# board.net
KiCad netlist of a schematic drawn in EAGLE
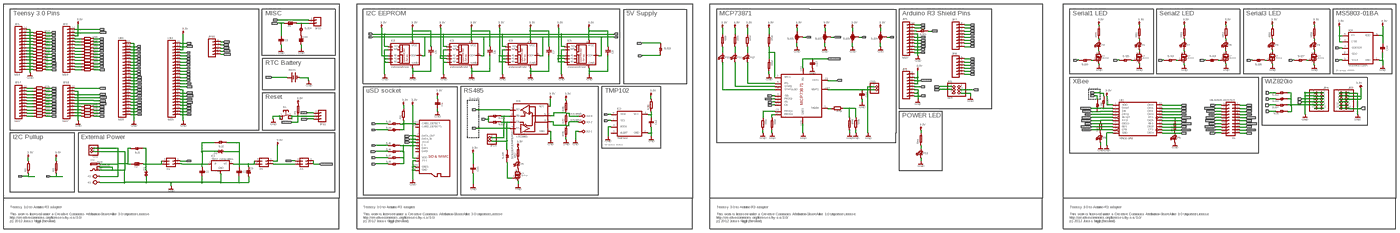
[diagram p0: schematic, sheet 1, overview]
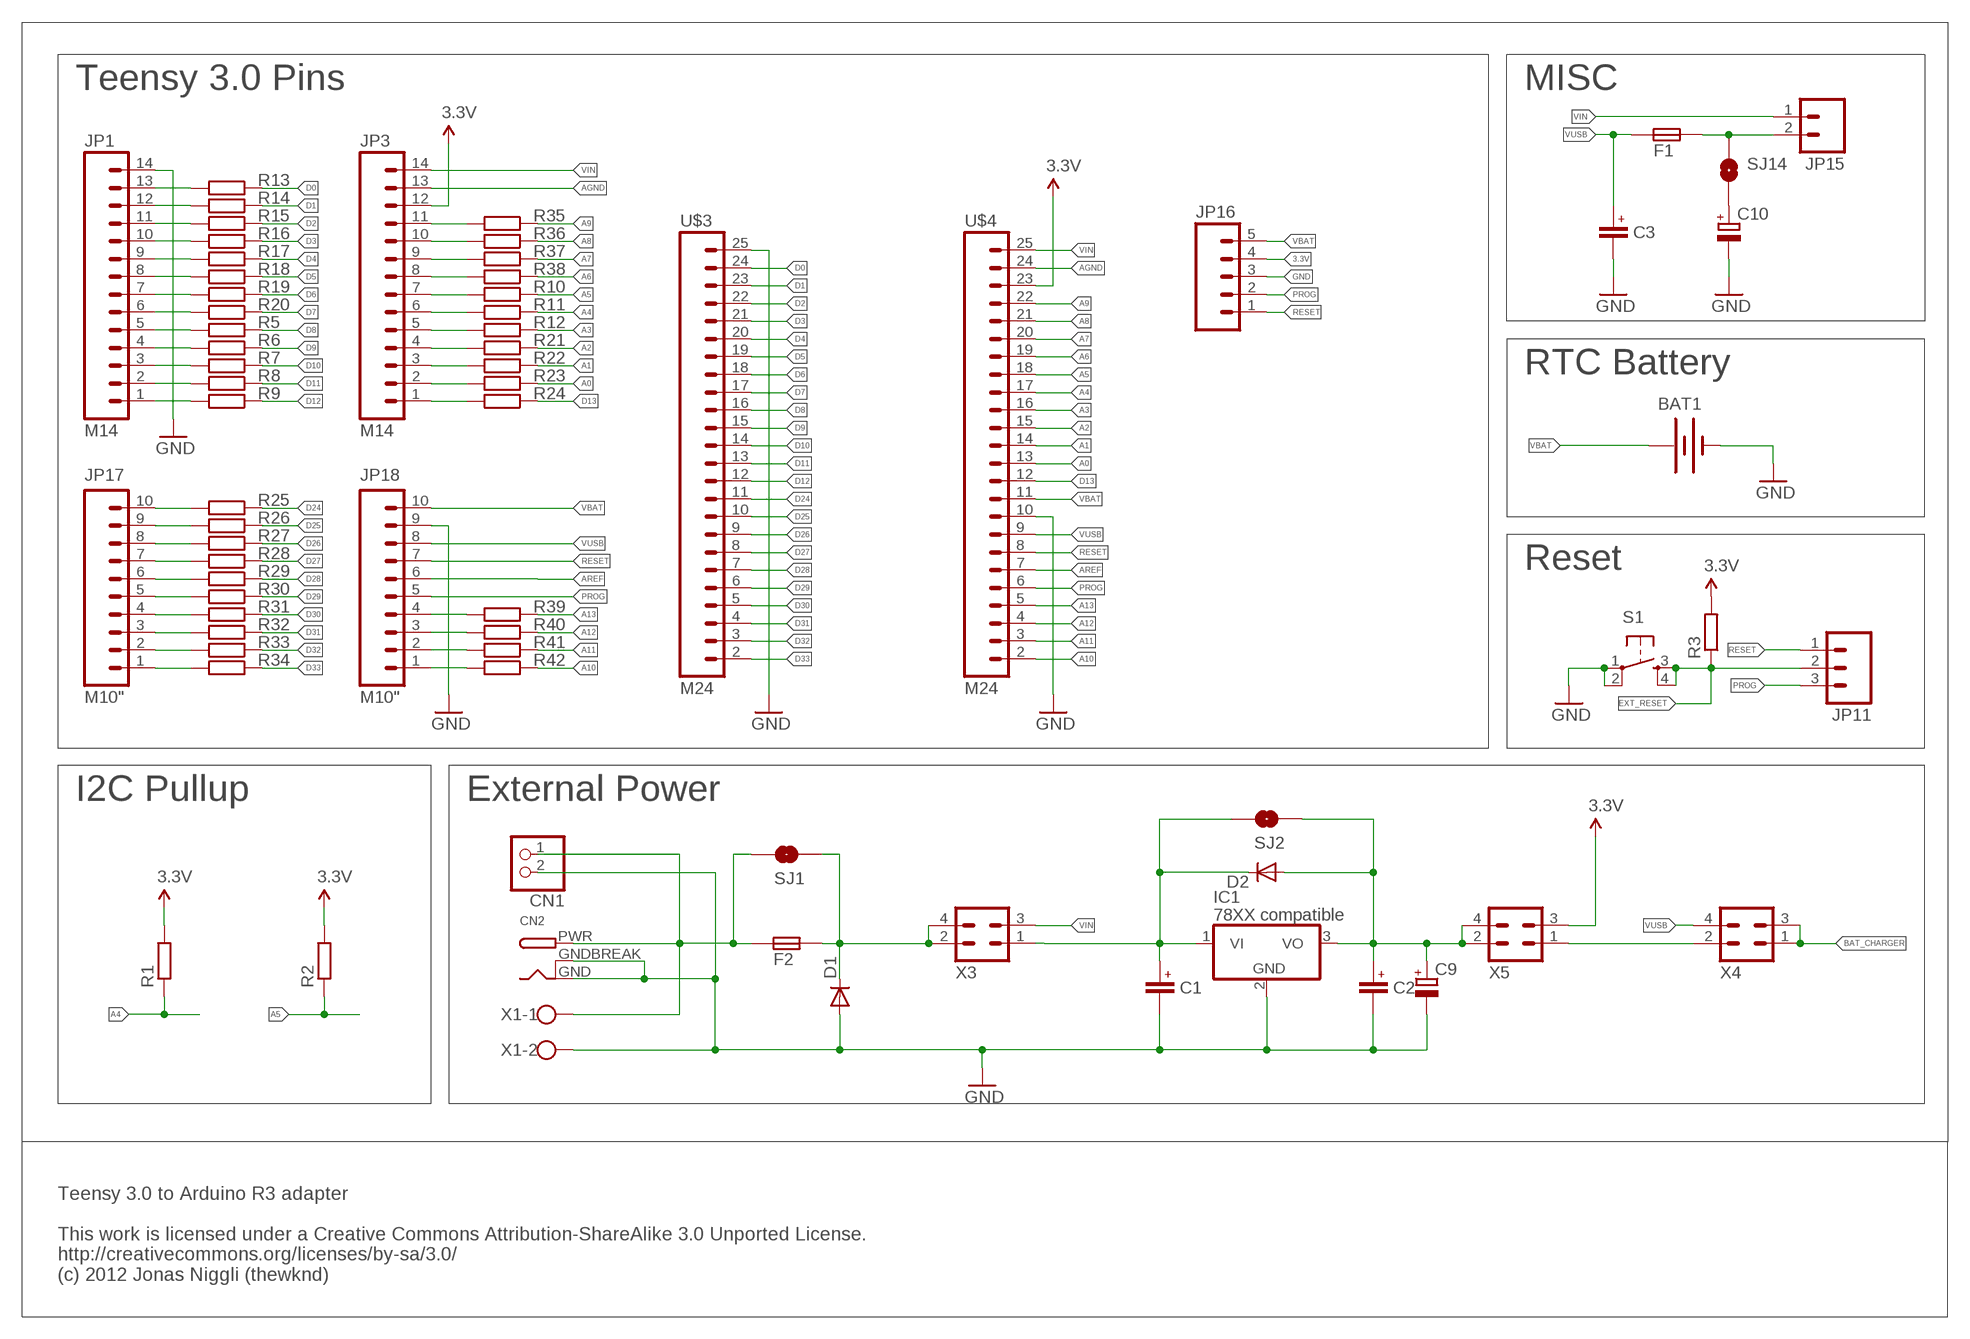
[diagram p1: schematic, sheet 1, part 1 of 4]
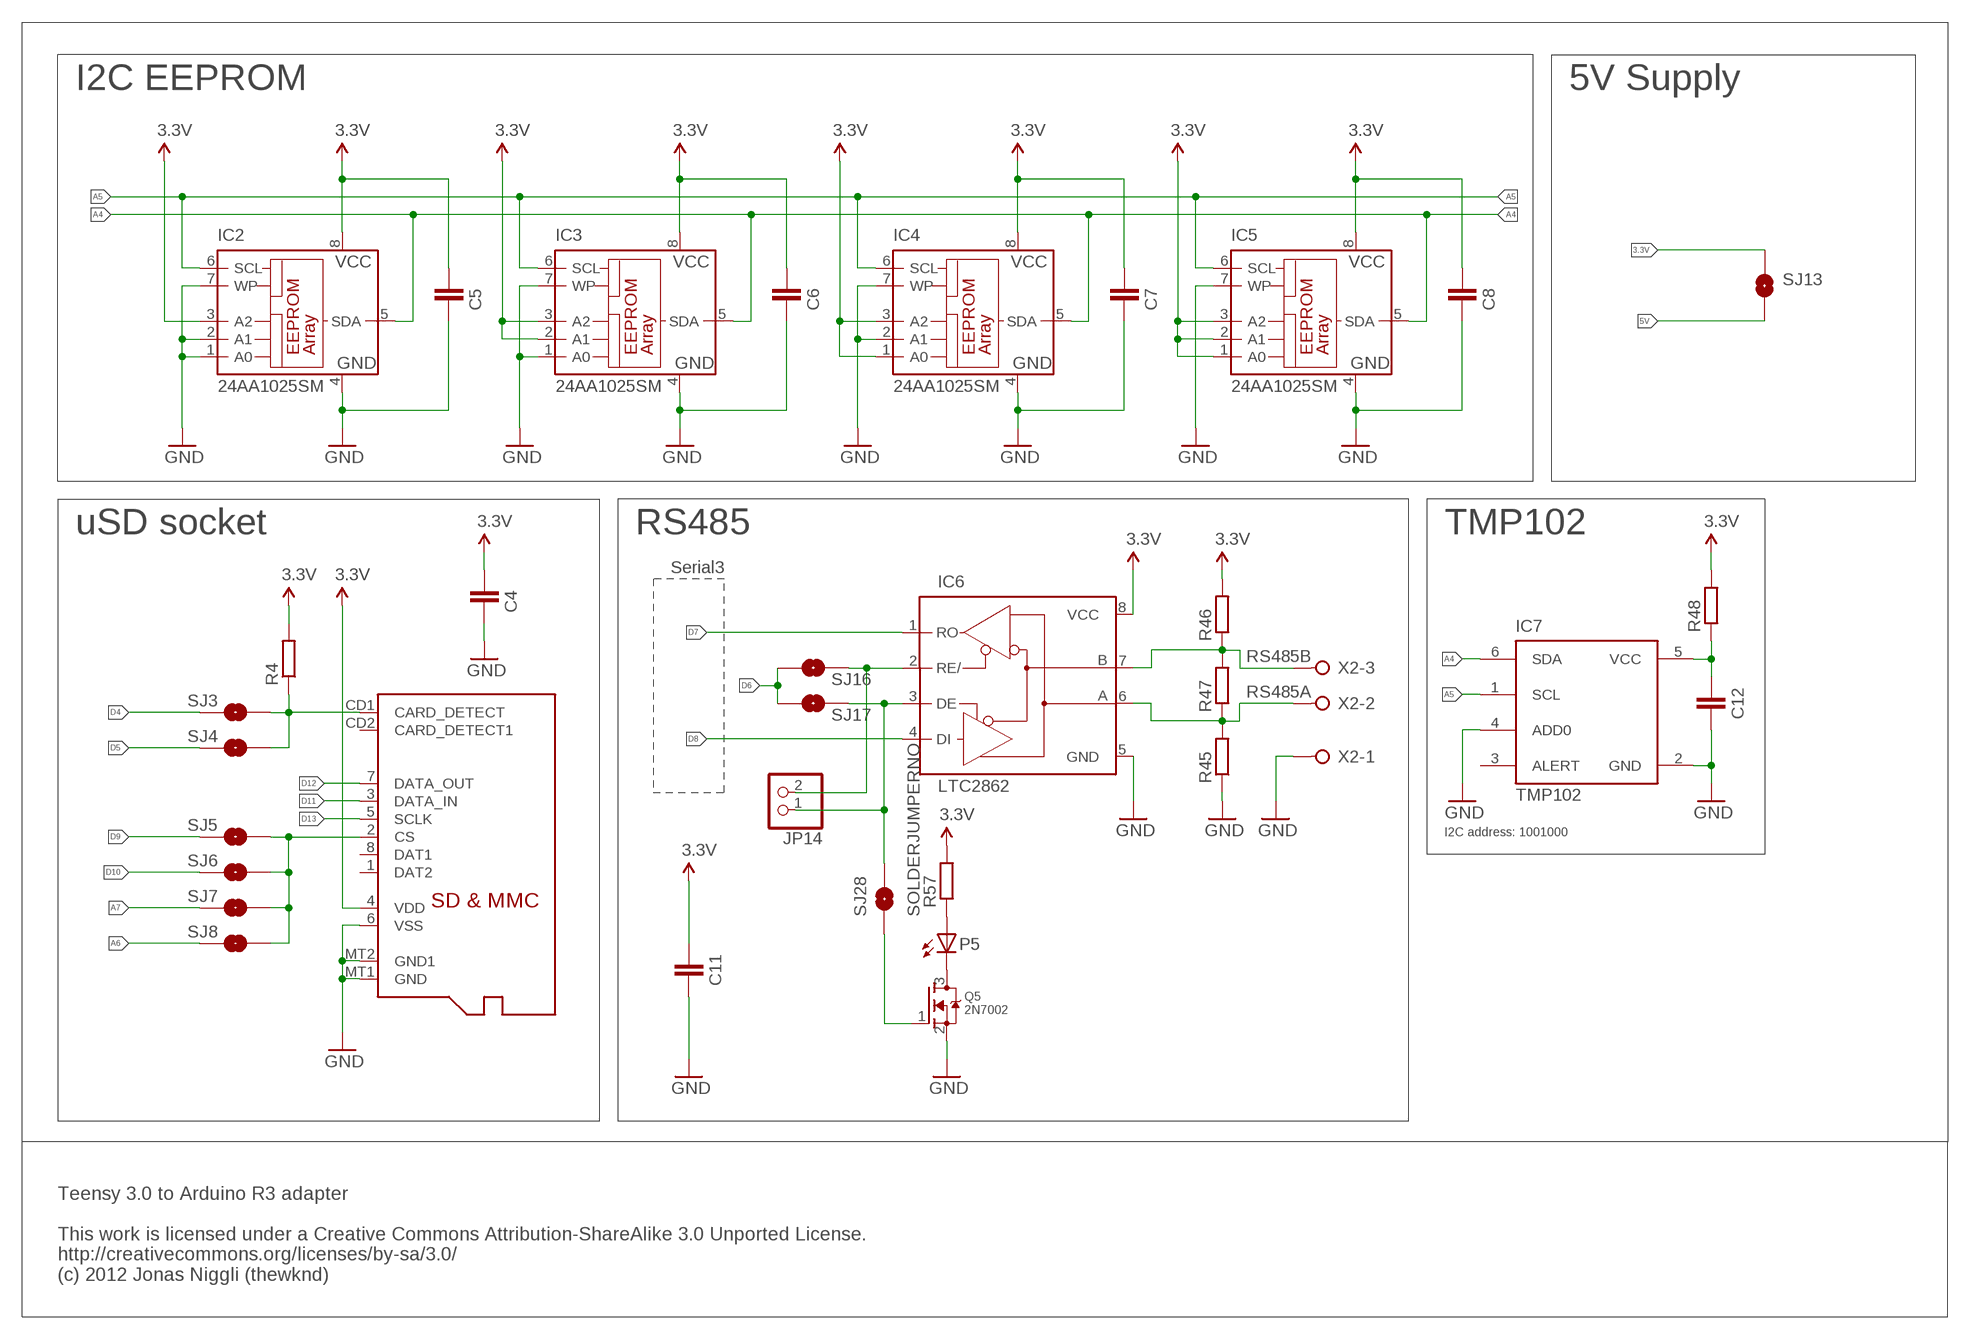
[diagram p2: schematic, sheet 1, part 2 of 4]
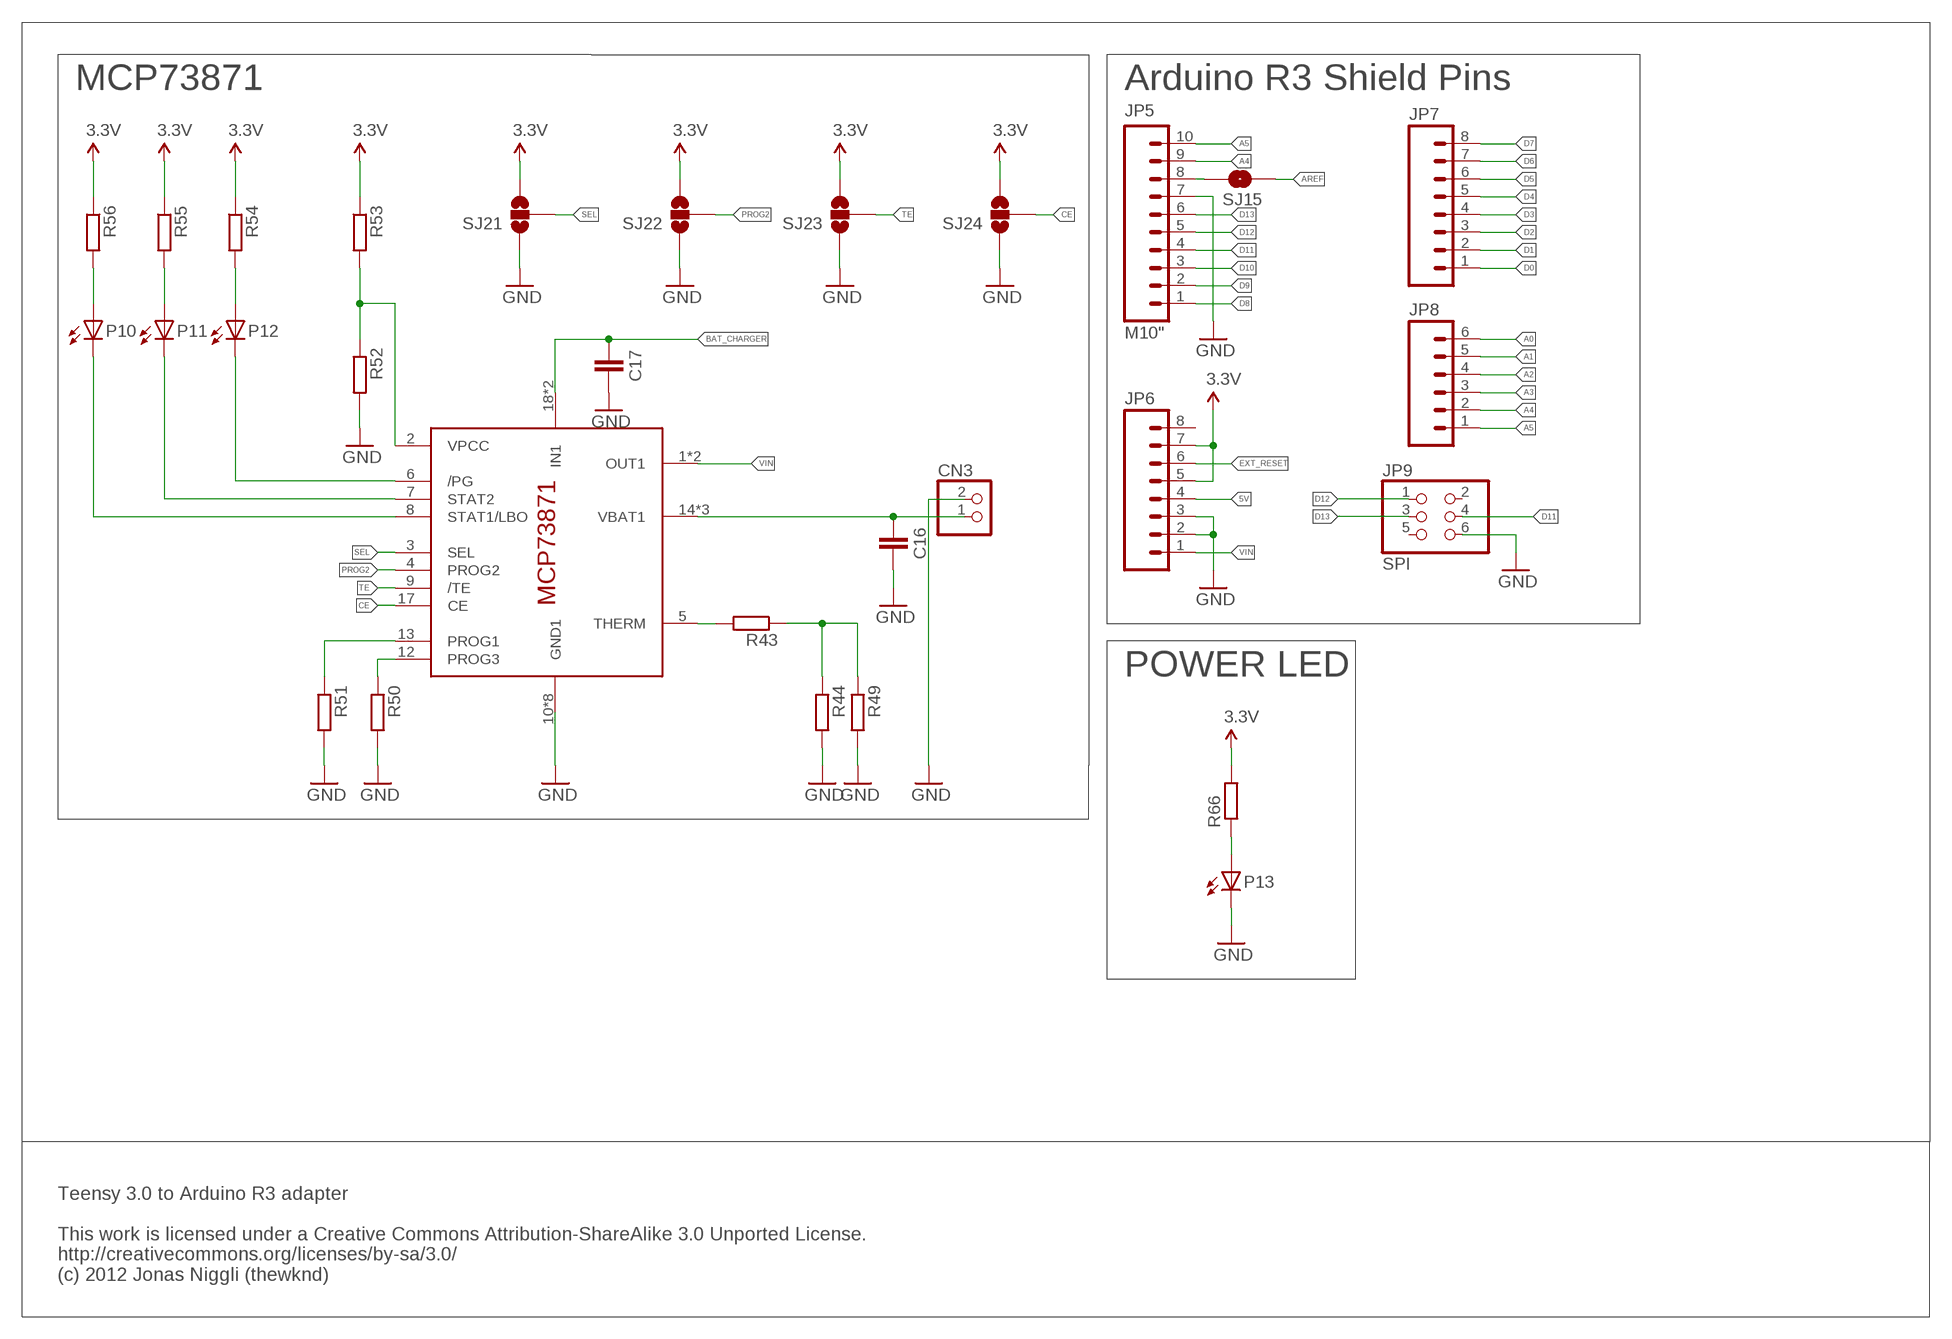
[diagram p3: schematic, sheet 1, part 3 of 4]
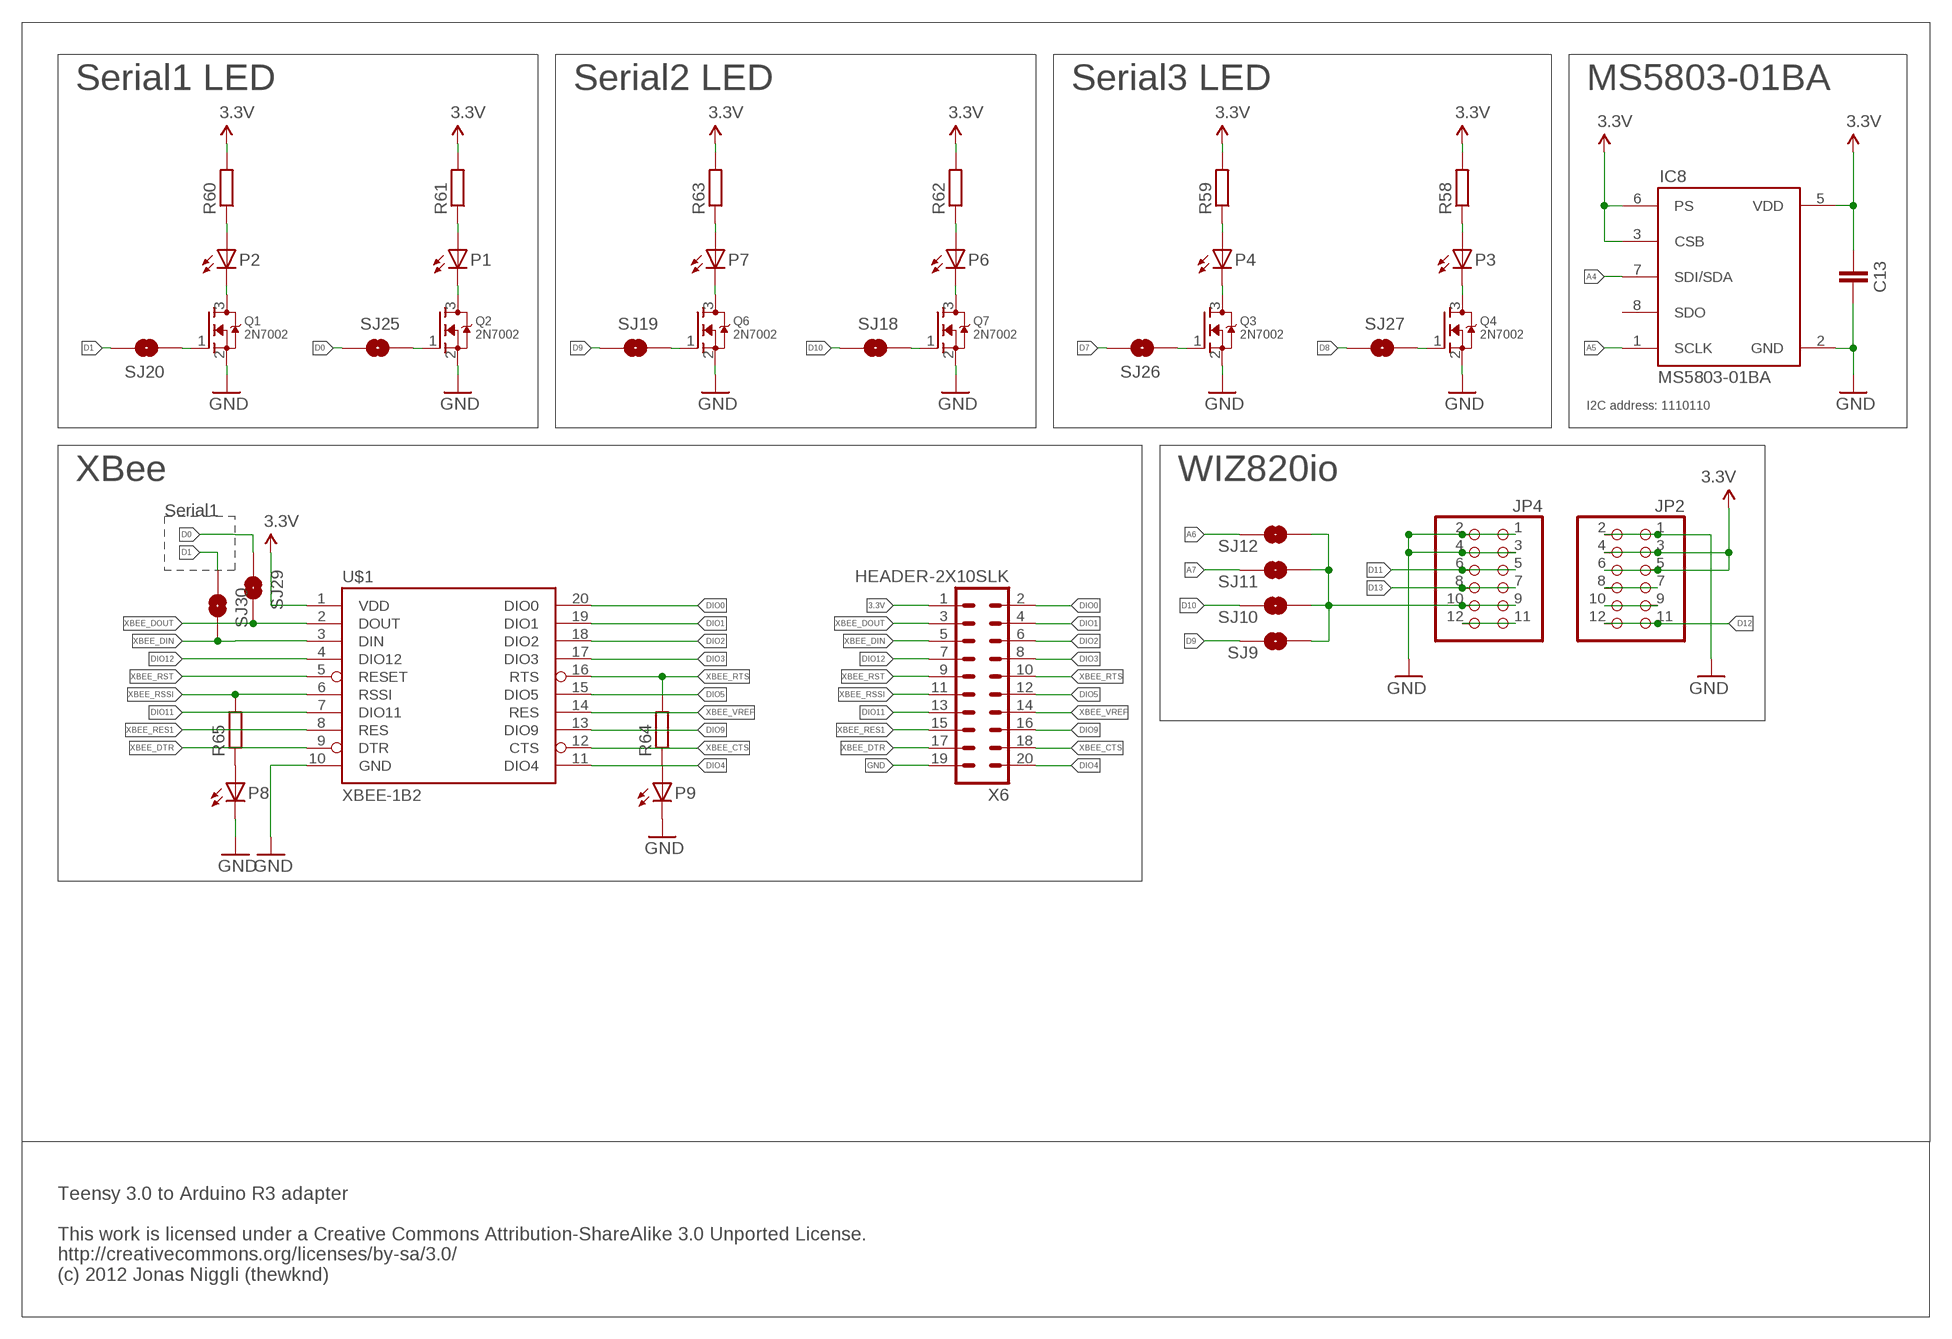
[diagram p4: schematic, sheet 1, part 4 of 4]

(export (version "E")
  (design (tool "Eeschema 10.0.6"))
  (components
    (comp (ref "BAT1")
      (value "BATTERY12MM")
      (footprint "eagle-import:BATTCON_12MM")
      (libsource (lib "eagle-import") (part "BATTERY12MM"))
    )
    (comp (ref "C1")
      (value "CAPACITOR_POL-3216-POL")
      (footprint "eagle-import:3216C-POL")
      (libsource (lib "eagle-import") (part "CAPACITOR_POL-3216-POL"))
    )
    (comp (ref "C2")
      (value "CAPACITOR_POL-3216-POL")
      (footprint "eagle-import:3216C-POL")
      (libsource (lib "eagle-import") (part "CAPACITOR_POL-3216-POL"))
    )
    (comp (ref "C3")
      (value "CAPACITOR_POL-3216-POL")
      (footprint "eagle-import:3216C-POL")
      (libsource (lib "eagle-import") (part "CAPACITOR_POL-3216-POL"))
    )
    (comp (ref "C4")
      (value "CAPACITOR-0805")
      (footprint "eagle-import:0805C")
      (libsource (lib "eagle-import") (part "CAPACITOR-0805"))
    )
    (comp (ref "C5")
      (value "CAPACITOR-0805")
      (footprint "eagle-import:0805C")
      (libsource (lib "eagle-import") (part "CAPACITOR-0805"))
    )
    (comp (ref "C6")
      (value "CAPACITOR-0805")
      (footprint "eagle-import:0805C")
      (libsource (lib "eagle-import") (part "CAPACITOR-0805"))
    )
    (comp (ref "C7")
      (value "CAPACITOR-0805")
      (footprint "eagle-import:0805C")
      (libsource (lib "eagle-import") (part "CAPACITOR-0805"))
    )
    (comp (ref "C8")
      (value "CAPACITOR-0805")
      (footprint "eagle-import:0805C")
      (libsource (lib "eagle-import") (part "CAPACITOR-0805"))
    )
    (comp (ref "C9")
      (value "CPOL-EUD")
      (footprint "eagle-import:PANASONIC_D")
      (libsource (lib "eagle-import") (part "resistor_CPOL-EUD"))
    )
    (comp (ref "C10")
      (value "CPOL-EU085CS-1AR")
      (footprint "eagle-import:085CS_1AR")
      (libsource (lib "eagle-import") (part "CPOL-EU085CS-1AR"))
    )
    (comp (ref "C11")
      (value "CAPACITOR-0805")
      (footprint "eagle-import:0805C")
      (libsource (lib "eagle-import") (part "CAPACITOR-0805"))
    )
    (comp (ref "C12")
      (value "CAPACITOR-0805")
      (footprint "eagle-import:0805C")
      (libsource (lib "eagle-import") (part "CAPACITOR-0805"))
    )
    (comp (ref "C13")
      (value "CAPACITOR-0805")
      (footprint "eagle-import:0805C")
      (libsource (lib "eagle-import") (part "CAPACITOR-0805"))
    )
    (comp (ref "C16")
      (value "CAPACITOR-0805")
      (footprint "eagle-import:0805C")
      (libsource (lib "eagle-import") (part "CAPACITOR-0805"))
    )
    (comp (ref "C17")
      (value "CAPACITOR-0805")
      (footprint "eagle-import:0805C")
      (libsource (lib "eagle-import") (part "CAPACITOR-0805"))
    )
    (comp (ref "CN1")
      (value "JST_2PIN-THM-RA")
      (footprint "eagle-import:JST-PH-2-THM-RA")
      (libsource (lib "eagle-import") (part "JST_2PIN-THM-RA"))
    )
    (comp (ref "CN2")
      (value "DCBARRELPTH")
      (footprint "eagle-import:DCJACK_2MM_PTH")
      (libsource (lib "eagle-import") (part "DCBARRELPTH"))
    )
    (comp (ref "CN3")
      (value "JST_2PIN-THM-RA")
      (footprint "eagle-import:JST-PH-2-THM-RA")
      (libsource (lib "eagle-import") (part "JST_2PIN-THM-RA"))
    )
    (comp (ref "D1")
      (value "DIODESMA-KIT")
      (footprint "eagle-import:SMA-DIODE-KIT")
      (libsource (lib "eagle-import") (part "DIODESMA-KIT"))
    )
    (comp (ref "D2")
      (value "DIODESMA-KIT")
      (footprint "eagle-import:SMA-DIODE-KIT")
      (libsource (lib "eagle-import") (part "DIODESMA-KIT"))
    )
    (comp (ref "F1")
      (value "FUSE1812")
      (footprint "eagle-import:1812STD")
      (libsource (lib "eagle-import") (part "FUSE1812"))
    )
    (comp (ref "F2")
      (value "FUSE1812")
      (footprint "eagle-import:1812STD")
      (libsource (lib "eagle-import") (part "FUSE1812"))
    )
    (comp (ref "IC1")
      (value "78XX compatible")
      (footprint "eagle-import:TO220V")
      (libsource (lib "eagle-import") (part "78TV05"))
    )
    (comp (ref "IC2")
      (value "24AA1025SM")
      (footprint "eagle-import:SOIC-8")
      (libsource (lib "eagle-import") (part "EEPROM24AAXXXSM"))
    )
    (comp (ref "IC3")
      (value "24AA1025SM")
      (footprint "eagle-import:SOIC-8")
      (libsource (lib "eagle-import") (part "EEPROM24AAXXXSM"))
    )
    (comp (ref "IC4")
      (value "24AA1025SM")
      (footprint "eagle-import:SOIC-8")
      (libsource (lib "eagle-import") (part "EEPROM24AAXXXSM"))
    )
    (comp (ref "IC5")
      (value "24AA1025SM")
      (footprint "eagle-import:SOIC-8")
      (libsource (lib "eagle-import") (part "EEPROM24AAXXXSM"))
    )
    (comp (ref "IC6")
      (value "LTC2862")
      (footprint "eagle-import:SO08")
      (fields (field (name "MPN") "MAX3468ESA+T"))
      (libsource (lib "eagle-import") (part "MAX34SA68E"))
    )
    (comp (ref "IC7")
      (value "TMP102")
      (footprint "eagle-import:SOT563")
      (libsource (lib "eagle-import") (part "TMP102"))
    )
    (comp (ref "IC8")
      (value "MS5803-01BA")
      (footprint "eagle-import:MS5803")
      (libsource (lib "eagle-import") (part "MS5803-01BA"))
    )
    (comp (ref "IC9")
      (value "MCP73871")
      (footprint "eagle-import:QFN-20")
      (libsource (lib "eagle-import") (part "MCP73871"))
    )
    (comp (ref "JP1")
      (value "M14")
      (footprint "eagle-import:1X14")
      (libsource (lib "eagle-import") (part "M14"))
    )
    (comp (ref "JP2")
      (value "PINHD-2X6")
      (footprint "eagle-import:2X06")
      (libsource (lib "eagle-import") (part "PINHD-2X6"))
    )
    (comp (ref "JP3")
      (value "M14")
      (footprint "eagle-import:1X14")
      (libsource (lib "eagle-import") (part "M14"))
    )
    (comp (ref "JP4")
      (value "PINHD-2X6")
      (footprint "eagle-import:2X06")
      (libsource (lib "eagle-import") (part "PINHD-2X6"))
    )
    (comp (ref "JP5")
      (value "M10\"")
      (footprint "eagle-import:1X10")
      (libsource (lib "eagle-import") (part "M10{dblquote}"))
    )
    (comp (ref "JP6")
      (value "M081X08")
      (footprint "eagle-import:1X08")
      (libsource (lib "eagle-import") (part "M081X08"))
    )
    (comp (ref "JP7")
      (value "M081X08")
      (footprint "eagle-import:1X08")
      (libsource (lib "eagle-import") (part "M081X08"))
    )
    (comp (ref "JP8")
      (value "M06SIP")
      (footprint "eagle-import:1X06")
      (libsource (lib "eagle-import") (part "M06SIP"))
    )
    (comp (ref "JP9")
      (value "SPI")
      (footprint "eagle-import:2X03")
      (libsource (lib "eagle-import") (part "PINHD-2X3"))
    )
    (comp (ref "JP11")
      (value "M03PTH")
      (footprint "eagle-import:1X03")
      (libsource (lib "eagle-import") (part "M03PTH"))
    )
    (comp (ref "JP14")
      (value "PINHD-1X2")
      (footprint "eagle-import:1X02")
      (libsource (lib "eagle-import") (part "PINHD-1X2"))
    )
    (comp (ref "JP15")
      (value "M02PTH")
      (footprint "eagle-import:1X02")
      (libsource (lib "eagle-import") (part "M02PTH"))
    )
    (comp (ref "JP16")
      (value "M05PTH")
      (footprint "eagle-import:1X05")
      (libsource (lib "eagle-import") (part "M05PTH"))
    )
    (comp (ref "JP17")
      (value "M10\"")
      (footprint "eagle-import:1X10")
      (libsource (lib "eagle-import") (part "M10{dblquote}"))
    )
    (comp (ref "JP18")
      (value "M10\"")
      (footprint "eagle-import:1X10")
      (libsource (lib "eagle-import") (part "M10{dblquote}"))
    )
    (comp (ref "P1")
      (value "LED")
      (footprint "eagle-import:LED0805")
      (libsource (lib "eagle-import") (part "LED"))
    )
    (comp (ref "P2")
      (value "LED")
      (footprint "eagle-import:LED0805")
      (libsource (lib "eagle-import") (part "LED"))
    )
    (comp (ref "P3")
      (value "LED")
      (footprint "eagle-import:LED0805")
      (libsource (lib "eagle-import") (part "LED"))
    )
    (comp (ref "P4")
      (value "LED")
      (footprint "eagle-import:LED0805")
      (libsource (lib "eagle-import") (part "LED"))
    )
    (comp (ref "P5")
      (value "LED")
      (footprint "eagle-import:LED0805")
      (libsource (lib "eagle-import") (part "LED"))
    )
    (comp (ref "P6")
      (value "LED")
      (footprint "eagle-import:LED0805")
      (libsource (lib "eagle-import") (part "LED"))
    )
    (comp (ref "P7")
      (value "LED")
      (footprint "eagle-import:LED0805")
      (libsource (lib "eagle-import") (part "LED"))
    )
    (comp (ref "P8")
      (value "LED")
      (footprint "eagle-import:LED0805")
      (libsource (lib "eagle-import") (part "LED"))
    )
    (comp (ref "P9")
      (value "LED")
      (footprint "eagle-import:LED0805")
      (libsource (lib "eagle-import") (part "LED"))
    )
    (comp (ref "P10")
      (value "LED")
      (footprint "eagle-import:LED0805")
      (libsource (lib "eagle-import") (part "LED"))
    )
    (comp (ref "P11")
      (value "LED")
      (footprint "eagle-import:LED0805")
      (libsource (lib "eagle-import") (part "LED"))
    )
    (comp (ref "P12")
      (value "LED")
      (footprint "eagle-import:LED0805")
      (libsource (lib "eagle-import") (part "LED"))
    )
    (comp (ref "P13")
      (value "LED")
      (footprint "eagle-import:LED0805")
      (libsource (lib "eagle-import") (part "LED"))
    )
    (comp (ref "Q1")
      (value "2N7002")
      (footprint "eagle-import:SOT23")
      (libsource (lib "eagle-import") (part "MOSFET-NREFLOW"))
    )
    (comp (ref "Q2")
      (value "2N7002")
      (footprint "eagle-import:SOT23")
      (libsource (lib "eagle-import") (part "MOSFET-NREFLOW"))
    )
    (comp (ref "Q3")
      (value "2N7002")
      (footprint "eagle-import:SOT23")
      (libsource (lib "eagle-import") (part "MOSFET-NREFLOW"))
    )
    (comp (ref "Q4")
      (value "2N7002")
      (footprint "eagle-import:SOT23")
      (libsource (lib "eagle-import") (part "MOSFET-NREFLOW"))
    )
    (comp (ref "Q5")
      (value "2N7002")
      (footprint "eagle-import:SOT23")
      (libsource (lib "eagle-import") (part "MOSFET-NREFLOW"))
    )
    (comp (ref "Q6")
      (value "2N7002")
      (footprint "eagle-import:SOT23")
      (libsource (lib "eagle-import") (part "MOSFET-NREFLOW"))
    )
    (comp (ref "Q7")
      (value "2N7002")
      (footprint "eagle-import:SOT23")
      (libsource (lib "eagle-import") (part "MOSFET-NREFLOW"))
    )
    (comp (ref "R1")
      (value "RESISTOR")
      (footprint "eagle-import:R0805")
      (libsource (lib "eagle-import") (part "RESISTOR"))
    )
    (comp (ref "R2")
      (value "RESISTOR")
      (footprint "eagle-import:R0805")
      (libsource (lib "eagle-import") (part "RESISTOR"))
    )
    (comp (ref "R3")
      (value "RESISTOR")
      (footprint "eagle-import:R0805")
      (libsource (lib "eagle-import") (part "RESISTOR"))
    )
    (comp (ref "R4")
      (value "R4")
      (footprint "eagle-import:R0805")
      (libsource (lib "eagle-import") (part "RESISTOR"))
    )
    (comp (ref "R5")
      (value "RESISTOR")
      (footprint "eagle-import:R0805")
      (libsource (lib "eagle-import") (part "RESISTOR"))
    )
    (comp (ref "R6")
      (value "RESISTOR")
      (footprint "eagle-import:R0805")
      (libsource (lib "eagle-import") (part "RESISTOR"))
    )
    (comp (ref "R7")
      (value "RESISTOR")
      (footprint "eagle-import:R0805")
      (libsource (lib "eagle-import") (part "RESISTOR"))
    )
    (comp (ref "R8")
      (value "RESISTOR")
      (footprint "eagle-import:R0805")
      (libsource (lib "eagle-import") (part "RESISTOR"))
    )
    (comp (ref "R9")
      (value "RESISTOR")
      (footprint "eagle-import:R0805")
      (libsource (lib "eagle-import") (part "RESISTOR"))
    )
    (comp (ref "R10")
      (value "RESISTOR")
      (footprint "eagle-import:R0805")
      (libsource (lib "eagle-import") (part "RESISTOR"))
    )
    (comp (ref "R11")
      (value "RESISTOR")
      (footprint "eagle-import:R0805")
      (libsource (lib "eagle-import") (part "RESISTOR"))
    )
    (comp (ref "R12")
      (value "RESISTOR")
      (footprint "eagle-import:R0805")
      (libsource (lib "eagle-import") (part "RESISTOR"))
    )
    (comp (ref "R13")
      (value "RESISTOR")
      (footprint "eagle-import:R0805")
      (libsource (lib "eagle-import") (part "RESISTOR"))
    )
    (comp (ref "R14")
      (value "RESISTOR")
      (footprint "eagle-import:R0805")
      (libsource (lib "eagle-import") (part "RESISTOR"))
    )
    (comp (ref "R15")
      (value "RESISTOR")
      (footprint "eagle-import:R0805")
      (libsource (lib "eagle-import") (part "RESISTOR"))
    )
    (comp (ref "R16")
      (value "RESISTOR")
      (footprint "eagle-import:R0805")
      (libsource (lib "eagle-import") (part "RESISTOR"))
    )
    (comp (ref "R17")
      (value "RESISTOR")
      (footprint "eagle-import:R0805")
      (libsource (lib "eagle-import") (part "RESISTOR"))
    )
    (comp (ref "R18")
      (value "RESISTOR")
      (footprint "eagle-import:R0805")
      (libsource (lib "eagle-import") (part "RESISTOR"))
    )
    (comp (ref "R19")
      (value "RESISTOR")
      (footprint "eagle-import:R0805")
      (libsource (lib "eagle-import") (part "RESISTOR"))
    )
    (comp (ref "R20")
      (value "RESISTOR")
      (footprint "eagle-import:R0805")
      (libsource (lib "eagle-import") (part "RESISTOR"))
    )
    (comp (ref "R21")
      (value "RESISTOR")
      (footprint "eagle-import:R0805")
      (libsource (lib "eagle-import") (part "RESISTOR"))
    )
    (comp (ref "R22")
      (value "RESISTOR")
      (footprint "eagle-import:R0805")
      (libsource (lib "eagle-import") (part "RESISTOR"))
    )
    (comp (ref "R23")
      (value "RESISTOR")
      (footprint "eagle-import:R0805")
      (libsource (lib "eagle-import") (part "RESISTOR"))
    )
    (comp (ref "R24")
      (value "RESISTOR")
      (footprint "eagle-import:R0805")
      (libsource (lib "eagle-import") (part "RESISTOR"))
    )
    (comp (ref "R25")
      (value "RESISTOR")
      (footprint "eagle-import:R0805")
      (libsource (lib "eagle-import") (part "RESISTOR"))
    )
    (comp (ref "R26")
      (value "RESISTOR")
      (footprint "eagle-import:R0805")
      (libsource (lib "eagle-import") (part "RESISTOR"))
    )
    (comp (ref "R27")
      (value "RESISTOR")
      (footprint "eagle-import:R0805")
      (libsource (lib "eagle-import") (part "RESISTOR"))
    )
    (comp (ref "R28")
      (value "RESISTOR")
      (footprint "eagle-import:R0805")
      (libsource (lib "eagle-import") (part "RESISTOR"))
    )
    (comp (ref "R29")
      (value "RESISTOR")
      (footprint "eagle-import:R0805")
      (libsource (lib "eagle-import") (part "RESISTOR"))
    )
    (comp (ref "R30")
      (value "RESISTOR")
      (footprint "eagle-import:R0805")
      (libsource (lib "eagle-import") (part "RESISTOR"))
    )
    (comp (ref "R31")
      (value "RESISTOR")
      (footprint "eagle-import:R0805")
      (libsource (lib "eagle-import") (part "RESISTOR"))
    )
    (comp (ref "R32")
      (value "RESISTOR")
      (footprint "eagle-import:R0805")
      (libsource (lib "eagle-import") (part "RESISTOR"))
    )
    (comp (ref "R33")
      (value "RESISTOR")
      (footprint "eagle-import:R0805")
      (libsource (lib "eagle-import") (part "RESISTOR"))
    )
    (comp (ref "R34")
      (value "RESISTOR")
      (footprint "eagle-import:R0805")
      (libsource (lib "eagle-import") (part "RESISTOR"))
    )
    (comp (ref "R35")
      (value "RESISTOR")
      (footprint "eagle-import:R0805")
      (libsource (lib "eagle-import") (part "RESISTOR"))
    )
    (comp (ref "R36")
      (value "RESISTOR")
      (footprint "eagle-import:R0805")
      (libsource (lib "eagle-import") (part "RESISTOR"))
    )
    (comp (ref "R37")
      (value "RESISTOR")
      (footprint "eagle-import:R0805")
      (libsource (lib "eagle-import") (part "RESISTOR"))
    )
    (comp (ref "R38")
      (value "RESISTOR")
      (footprint "eagle-import:R0805")
      (libsource (lib "eagle-import") (part "RESISTOR"))
    )
    (comp (ref "R39")
      (value "RESISTOR")
      (footprint "eagle-import:R0805")
      (libsource (lib "eagle-import") (part "RESISTOR"))
    )
    (comp (ref "R40")
      (value "RESISTOR")
      (footprint "eagle-import:R0805")
      (libsource (lib "eagle-import") (part "RESISTOR"))
    )
    (comp (ref "R41")
      (value "RESISTOR")
      (footprint "eagle-import:R0805")
      (libsource (lib "eagle-import") (part "RESISTOR"))
    )
    (comp (ref "R42")
      (value "RESISTOR")
      (footprint "eagle-import:R0805")
      (libsource (lib "eagle-import") (part "RESISTOR"))
    )
    (comp (ref "R43")
      (value "RESISTOR")
      (footprint "eagle-import:R0805")
      (libsource (lib "eagle-import") (part "RESISTOR"))
    )
    (comp (ref "R44")
      (value "RESISTOR")
      (footprint "eagle-import:R0805")
      (libsource (lib "eagle-import") (part "RESISTOR"))
    )
    (comp (ref "R45")
      (value "RESISTOR")
      (footprint "eagle-import:R0805")
      (libsource (lib "eagle-import") (part "RESISTOR"))
    )
    (comp (ref "R46")
      (value "RESISTOR")
      (footprint "eagle-import:R0805")
      (libsource (lib "eagle-import") (part "RESISTOR"))
    )
    (comp (ref "R47")
      (value "RESISTOR")
      (footprint "eagle-import:R0805")
      (libsource (lib "eagle-import") (part "RESISTOR"))
    )
    (comp (ref "R48")
      (value "RESISTOR")
      (footprint "eagle-import:R0805")
      (libsource (lib "eagle-import") (part "RESISTOR"))
    )
    (comp (ref "R49")
      (value "RESISTOR")
      (footprint "eagle-import:R0805")
      (libsource (lib "eagle-import") (part "RESISTOR"))
    )
    (comp (ref "R50")
      (value "RESISTOR")
      (footprint "eagle-import:R0805")
      (libsource (lib "eagle-import") (part "RESISTOR"))
    )
    (comp (ref "R51")
      (value "RESISTOR")
      (footprint "eagle-import:R0805")
      (libsource (lib "eagle-import") (part "RESISTOR"))
    )
    (comp (ref "R52")
      (value "RESISTOR")
      (footprint "eagle-import:R0805")
      (libsource (lib "eagle-import") (part "RESISTOR"))
    )
    (comp (ref "R53")
      (value "RESISTOR")
      (footprint "eagle-import:R0805")
      (libsource (lib "eagle-import") (part "RESISTOR"))
    )
    (comp (ref "R54")
      (value "RESISTOR")
      (footprint "eagle-import:R0805")
      (libsource (lib "eagle-import") (part "RESISTOR"))
    )
    (comp (ref "R55")
      (value "RESISTOR")
      (footprint "eagle-import:R0805")
      (libsource (lib "eagle-import") (part "RESISTOR"))
    )
    (comp (ref "R56")
      (value "RESISTOR")
      (footprint "eagle-import:R0805")
      (libsource (lib "eagle-import") (part "RESISTOR"))
    )
    (comp (ref "R57")
      (value "RESISTOR")
      (footprint "eagle-import:R0805")
      (libsource (lib "eagle-import") (part "RESISTOR"))
    )
    (comp (ref "R58")
      (value "RESISTOR")
      (footprint "eagle-import:R0805")
      (libsource (lib "eagle-import") (part "RESISTOR"))
    )
    (comp (ref "R59")
      (value "RESISTOR")
      (footprint "eagle-import:R0805")
      (libsource (lib "eagle-import") (part "RESISTOR"))
    )
    (comp (ref "R60")
      (value "RESISTOR")
      (footprint "eagle-import:R0805")
      (libsource (lib "eagle-import") (part "RESISTOR"))
    )
    (comp (ref "R61")
      (value "RESISTOR")
      (footprint "eagle-import:R0805")
      (libsource (lib "eagle-import") (part "RESISTOR"))
    )
    (comp (ref "R62")
      (value "RESISTOR")
      (footprint "eagle-import:R0805")
      (libsource (lib "eagle-import") (part "RESISTOR"))
    )
    (comp (ref "R63")
      (value "RESISTOR")
      (footprint "eagle-import:R0805")
      (libsource (lib "eagle-import") (part "RESISTOR"))
    )
    (comp (ref "R64")
      (value "RESISTOR")
      (footprint "eagle-import:R0805")
      (libsource (lib "eagle-import") (part "RESISTOR"))
    )
    (comp (ref "R65")
      (value "RESISTOR")
      (footprint "eagle-import:R0805")
      (libsource (lib "eagle-import") (part "RESISTOR"))
    )
    (comp (ref "R66")
      (value "RESISTOR")
      (footprint "eagle-import:R0805")
      (libsource (lib "eagle-import") (part "RESISTOR"))
    )
    (comp (ref "S1")
      (value "TAC_SWITCHPTH")
      (footprint "eagle-import:TACTILE-PTH")
      (libsource (lib "eagle-import") (part "TAC_SWITCHPTH"))
    )
    (comp (ref "SJ1")
      (value "SOLDERJUMPERNO")
      (footprint "eagle-import:SJ_2S-NO")
      (libsource (lib "eagle-import") (part "SOLDERJUMPERNO"))
    )
    (comp (ref "SJ2")
      (value "SOLDERJUMPERNO")
      (footprint "eagle-import:SJ_2S-NO")
      (libsource (lib "eagle-import") (part "SOLDERJUMPERNO"))
    )
    (comp (ref "SJ3")
      (value "SOLDERJUMPERNO")
      (footprint "eagle-import:SJ_2S-NO")
      (libsource (lib "eagle-import") (part "SOLDERJUMPERNO"))
    )
    (comp (ref "SJ4")
      (value "SOLDERJUMPERNO")
      (footprint "eagle-import:SJ_2S-NO")
      (libsource (lib "eagle-import") (part "SOLDERJUMPERNO"))
    )
    (comp (ref "SJ5")
      (value "SOLDERJUMPERNO")
      (footprint "eagle-import:SJ_2S-NO")
      (libsource (lib "eagle-import") (part "SOLDERJUMPERNO"))
    )
    (comp (ref "SJ6")
      (value "SOLDERJUMPERNO")
      (footprint "eagle-import:SJ_2S-NO")
      (libsource (lib "eagle-import") (part "SOLDERJUMPERNO"))
    )
    (comp (ref "SJ7")
      (value "SOLDERJUMPERNO")
      (footprint "eagle-import:SJ_2S-NO")
      (libsource (lib "eagle-import") (part "SOLDERJUMPERNO"))
    )
    (comp (ref "SJ8")
      (value "SOLDERJUMPERNO")
      (footprint "eagle-import:SJ_2S-NO")
      (libsource (lib "eagle-import") (part "SOLDERJUMPERNO"))
    )
    (comp (ref "SJ9")
      (value "SOLDERJUMPERNO")
      (footprint "eagle-import:SJ_2S-NO")
      (libsource (lib "eagle-import") (part "SOLDERJUMPERNO"))
    )
    (comp (ref "SJ10")
      (value "SOLDERJUMPERNO")
      (footprint "eagle-import:SJ_2S-NO")
      (libsource (lib "eagle-import") (part "SOLDERJUMPERNO"))
    )
    (comp (ref "SJ11")
      (value "SOLDERJUMPERNO")
      (footprint "eagle-import:SJ_2S-NO")
      (libsource (lib "eagle-import") (part "SOLDERJUMPERNO"))
    )
    (comp (ref "SJ12")
      (value "SOLDERJUMPERNO")
      (footprint "eagle-import:SJ_2S-NO")
      (libsource (lib "eagle-import") (part "SOLDERJUMPERNO"))
    )
    (comp (ref "SJ13")
      (value "SOLDERJUMPERNO")
      (footprint "eagle-import:SJ_2S-NO")
      (libsource (lib "eagle-import") (part "SOLDERJUMPERNO"))
    )
    (comp (ref "SJ14")
      (value "SOLDERJUMPERNO")
      (footprint "eagle-import:SJ_2S-NO")
      (libsource (lib "eagle-import") (part "SOLDERJUMPERNO"))
    )
    (comp (ref "SJ15")
      (value "SOLDERJUMPERNO")
      (footprint "eagle-import:SJ_2S-NO")
      (libsource (lib "eagle-import") (part "SOLDERJUMPERNO"))
    )
    (comp (ref "SJ16")
      (value "SOLDERJUMPERNO")
      (footprint "eagle-import:SJ_2S-NO")
      (libsource (lib "eagle-import") (part "SOLDERJUMPERNO"))
    )
    (comp (ref "SJ17")
      (value "SOLDERJUMPERNO")
      (footprint "eagle-import:SJ_2S-NO")
      (libsource (lib "eagle-import") (part "SOLDERJUMPERNO"))
    )
    (comp (ref "SJ18")
      (value "SOLDERJUMPERNO")
      (footprint "eagle-import:SJ_2S-NO")
      (libsource (lib "eagle-import") (part "SOLDERJUMPERNO"))
    )
    (comp (ref "SJ19")
      (value "SOLDERJUMPERNO")
      (footprint "eagle-import:SJ_2S-NO")
      (libsource (lib "eagle-import") (part "SOLDERJUMPERNO"))
    )
    (comp (ref "SJ20")
      (value "SOLDERJUMPERNO")
      (footprint "eagle-import:SJ_2S-NO")
      (libsource (lib "eagle-import") (part "SOLDERJUMPERNO"))
    )
    (comp (ref "SJ21")
      (value "SOLDERJUMPER_2WAYT")
      (footprint "eagle-import:SJ_2")
      (libsource (lib "eagle-import") (part "SOLDERJUMPER_2WAYT"))
    )
    (comp (ref "SJ22")
      (value "SOLDERJUMPER_2WAYT")
      (footprint "eagle-import:SJ_2")
      (libsource (lib "eagle-import") (part "SOLDERJUMPER_2WAYT"))
    )
    (comp (ref "SJ23")
      (value "SOLDERJUMPER_2WAYT")
      (footprint "eagle-import:SJ_2")
      (libsource (lib "eagle-import") (part "SOLDERJUMPER_2WAYT"))
    )
    (comp (ref "SJ24")
      (value "SOLDERJUMPER_2WAYT")
      (footprint "eagle-import:SJ_2")
      (libsource (lib "eagle-import") (part "SOLDERJUMPER_2WAYT"))
    )
    (comp (ref "SJ25")
      (value "SOLDERJUMPERNO")
      (footprint "eagle-import:SJ_2S-NO")
      (libsource (lib "eagle-import") (part "SOLDERJUMPERNO"))
    )
    (comp (ref "SJ26")
      (value "SOLDERJUMPERNO")
      (footprint "eagle-import:SJ_2S-NO")
      (libsource (lib "eagle-import") (part "SOLDERJUMPERNO"))
    )
    (comp (ref "SJ27")
      (value "SOLDERJUMPERNO")
      (footprint "eagle-import:SJ_2S-NO")
      (libsource (lib "eagle-import") (part "SOLDERJUMPERNO"))
    )
    (comp (ref "SJ28")
      (value "SOLDERJUMPERNO")
      (footprint "eagle-import:SJ_2S-NO")
      (libsource (lib "eagle-import") (part "SOLDERJUMPERNO"))
    )
    (comp (ref "SJ29")
      (value "SOLDERJUMPERNO")
      (footprint "eagle-import:SJ_2S-NO")
      (libsource (lib "eagle-import") (part "SOLDERJUMPERNO"))
    )
    (comp (ref "SJ30")
      (value "SOLDERJUMPERNO")
      (footprint "eagle-import:SJ_2S-NO")
      (libsource (lib "eagle-import") (part "SOLDERJUMPERNO"))
    )
    (comp (ref "U$1")
      (value "XBEE-1B2")
      (footprint "eagle-import:XBEE-SILK")
      (libsource (lib "eagle-import") (part "XBEE-1B2"))
    )
    (comp (ref "U$3")
      (value "M24")
      (footprint "eagle-import:1X24")
      (libsource (lib "eagle-import") (part "M24"))
    )
    (comp (ref "U$4")
      (value "M24")
      (footprint "eagle-import:1X24")
      (libsource (lib "eagle-import") (part "M24"))
    )
    (comp (ref "U1")
      (value "MICROSD")
      (footprint "eagle-import:MICROSD")
      (libsource (lib "eagle-import") (part "MICROSD"))
    )
    (comp (ref "X1")
      (value "W237-102")
      (footprint "eagle-import:W237-102")
      (fields (field (name "MPN") "237-102"))
      (libsource (lib "eagle-import") (part "W237-102"))
    )
    (comp (ref "X2")
      (value "W237-03P")
      (footprint "eagle-import:W237-133")
      (fields (field (name "OC_NEWARK") "unknown"))
      (libsource (lib "eagle-import") (part "W237-03P"))
    )
    (comp (ref "X3")
      (value "HEADER-2X2")
      (footprint "eagle-import:HEADER-PTH-2X2")
      (libsource (lib "eagle-import") (part "HEADER-2X2"))
    )
    (comp (ref "X4")
      (value "HEADER-2X2")
      (footprint "eagle-import:HEADER-PTH-2X2")
      (libsource (lib "eagle-import") (part "HEADER-2X2"))
    )
    (comp (ref "X5")
      (value "HEADER-2X2")
      (footprint "eagle-import:HEADER-PTH-2X2")
      (libsource (lib "eagle-import") (part "HEADER-2X2"))
    )
    (comp (ref "X6")
      (value "HEADER-2X10SLK")
      (footprint "eagle-import:HEADER-PTH-2X10")
      (libsource (lib "eagle-import") (part "HEADER-2X10SLK"))
    )
  )
  (nets
    (net (code "1") (name "3.3V") (class "Default")
      (node (ref "C11") (pin "1") (pinfunction "1_1") (pintype "passive"))
      (node (ref "C13") (pin "1") (pinfunction "1_1") (pintype "passive"))
      (node (ref "C4") (pin "1") (pinfunction "1_1") (pintype "passive"))
      (node (ref "C5") (pin "1") (pinfunction "1_1") (pintype "passive"))
      (node (ref "C6") (pin "1") (pinfunction "1_1") (pintype "passive"))
      (node (ref "C7") (pin "1") (pinfunction "1_1") (pintype "passive"))
      (node (ref "C8") (pin "1") (pinfunction "1_1") (pintype "passive"))
      (node (ref "IC2") (pin "3") (pinfunction "A2_3") (pintype "input"))
      (node (ref "IC2") (pin "8") (pinfunction "VCC_8") (pintype "power_in"))
      (node (ref "IC3") (pin "2") (pinfunction "A1_2") (pintype "input"))
      (node (ref "IC3") (pin "3") (pinfunction "A2_3") (pintype "input"))
      (node (ref "IC3") (pin "8") (pinfunction "VCC_8") (pintype "power_in"))
      (node (ref "IC4") (pin "1") (pinfunction "A0_1") (pintype "input"))
      (node (ref "IC4") (pin "3") (pinfunction "A2_3") (pintype "input"))
      (node (ref "IC4") (pin "8") (pinfunction "VCC_8") (pintype "power_in"))
      (node (ref "IC5") (pin "1") (pinfunction "A0_1") (pintype "input"))
      (node (ref "IC5") (pin "2") (pinfunction "A1_2") (pintype "input"))
      (node (ref "IC5") (pin "3") (pinfunction "A2_3") (pintype "input"))
      (node (ref "IC5") (pin "8") (pinfunction "VCC_8") (pintype "power_in"))
      (node (ref "IC6") (pin "8") (pinfunction "VCC_8") (pintype "power_in"))
      (node (ref "IC8") (pin "3") (pinfunction "CSB_3") (pintype "input"))
      (node (ref "IC8") (pin "5") (pinfunction "VDD_5") (pintype "power_in"))
      (node (ref "IC8") (pin "6") (pinfunction "PS_6") (pintype "input"))
      (node (ref "JP16") (pin "4") (pinfunction "4_4") (pintype "passive"))
      (node (ref "JP2") (pin "3") (pinfunction "3_3") (pintype "passive"))
      (node (ref "JP2") (pin "4") (pinfunction "4_4") (pintype "passive"))
      (node (ref "JP2") (pin "5") (pinfunction "5_5") (pintype "passive"))
      (node (ref "JP2") (pin "6") (pinfunction "6_6") (pintype "passive"))
      (node (ref "JP3") (pin "12") (pinfunction "12_12") (pintype "passive"))
      (node (ref "JP6") (pin "5") (pinfunction "5_5") (pintype "passive"))
      (node (ref "JP6") (pin "7") (pinfunction "7_7") (pintype "passive"))
      (node (ref "R1") (pin "2") (pinfunction "2_2") (pintype "passive"))
      (node (ref "R2") (pin "2") (pinfunction "2_2") (pintype "passive"))
      (node (ref "R3") (pin "2") (pinfunction "2_2") (pintype "passive"))
      (node (ref "R4") (pin "2") (pinfunction "2_2") (pintype "passive"))
      (node (ref "R46") (pin "2") (pinfunction "2_2") (pintype "passive"))
      (node (ref "R48") (pin "2") (pinfunction "2_2") (pintype "passive"))
      (node (ref "R53") (pin "1") (pinfunction "1_1") (pintype "passive"))
      (node (ref "R54") (pin "1") (pinfunction "1_1") (pintype "passive"))
      (node (ref "R55") (pin "1") (pinfunction "1_1") (pintype "passive"))
      (node (ref "R56") (pin "1") (pinfunction "1_1") (pintype "passive"))
      (node (ref "R57") (pin "2") (pinfunction "2_2") (pintype "passive"))
      (node (ref "R58") (pin "2") (pinfunction "2_2") (pintype "passive"))
      (node (ref "R59") (pin "2") (pinfunction "2_2") (pintype "passive"))
      (node (ref "R60") (pin "2") (pinfunction "2_2") (pintype "passive"))
      (node (ref "R61") (pin "2") (pinfunction "2_2") (pintype "passive"))
      (node (ref "R62") (pin "2") (pinfunction "2_2") (pintype "passive"))
      (node (ref "R63") (pin "2") (pinfunction "2_2") (pintype "passive"))
      (node (ref "R66") (pin "2") (pinfunction "2_2") (pintype "passive"))
      (node (ref "SJ13") (pin "1") (pinfunction "1_1") (pintype "passive"))
      (node (ref "SJ21") (pin "3") (pinfunction "3_3") (pintype "passive"))
      (node (ref "SJ22") (pin "3") (pinfunction "3_3") (pintype "passive"))
      (node (ref "SJ23") (pin "3") (pinfunction "3_3") (pintype "passive"))
      (node (ref "SJ24") (pin "3") (pinfunction "3_3") (pintype "passive"))
      (node (ref "U$1") (pin "1") (pinfunction "VDD_1") (pintype "power_in"))
      (node (ref "U$4") (pin "23") (pinfunction "23_23") (pintype "passive"))
      (node (ref "U1") (pin "4") (pinfunction "VDD_4") (pintype "power_in"))
      (node (ref "X5") (pin "3") (pinfunction "3_3") (pintype "passive"))
      (node (ref "X6") (pin "1") (pinfunction "1_1") (pintype "passive"))
    )
    (net (code "2") (name "5V") (class "Default")
      (node (ref "JP6") (pin "4") (pinfunction "4_4") (pintype "passive"))
      (node (ref "SJ13") (pin "2") (pinfunction "2_2") (pintype "passive"))
    )
    (net (code "3") (name "A0") (class "Default")
      (node (ref "JP8") (pin "6") (pinfunction "6_6") (pintype "passive"))
      (node (ref "R23") (pin "1") (pinfunction "1_1") (pintype "passive"))
      (node (ref "U$4") (pin "13") (pinfunction "13_13") (pintype "passive"))
    )
    (net (code "4") (name "A1") (class "Default")
      (node (ref "JP8") (pin "5") (pinfunction "5_5") (pintype "passive"))
      (node (ref "R22") (pin "1") (pinfunction "1_1") (pintype "passive"))
      (node (ref "U$4") (pin "14") (pinfunction "14_14") (pintype "passive"))
    )
    (net (code "5") (name "A2") (class "Default")
      (node (ref "JP8") (pin "4") (pinfunction "4_4") (pintype "passive"))
      (node (ref "R21") (pin "1") (pinfunction "1_1") (pintype "passive"))
      (node (ref "U$4") (pin "15") (pinfunction "15_15") (pintype "passive"))
    )
    (net (code "6") (name "A3") (class "Default")
      (node (ref "JP8") (pin "3") (pinfunction "3_3") (pintype "passive"))
      (node (ref "R12") (pin "1") (pinfunction "1_1") (pintype "passive"))
      (node (ref "U$4") (pin "16") (pinfunction "16_16") (pintype "passive"))
    )
    (net (code "7") (name "A4") (class "Default")
      (node (ref "IC2") (pin "5") (pinfunction "SDA_5") (pintype "bidirectional"))
      (node (ref "IC3") (pin "5") (pinfunction "SDA_5") (pintype "bidirectional"))
      (node (ref "IC4") (pin "5") (pinfunction "SDA_5") (pintype "bidirectional"))
      (node (ref "IC5") (pin "5") (pinfunction "SDA_5") (pintype "bidirectional"))
      (node (ref "IC7") (pin "6") (pinfunction "SDA_6") (pintype "bidirectional"))
      (node (ref "IC8") (pin "7") (pinfunction "SDI/SDA_7") (pintype "bidirectional"))
      (node (ref "JP5") (pin "9") (pinfunction "9_9") (pintype "passive"))
      (node (ref "JP8") (pin "2") (pinfunction "2_2") (pintype "passive"))
      (node (ref "R1") (pin "1") (pinfunction "1_1") (pintype "passive"))
      (node (ref "R11") (pin "1") (pinfunction "1_1") (pintype "passive"))
      (node (ref "U$4") (pin "17") (pinfunction "17_17") (pintype "passive"))
    )
    (net (code "8") (name "A5") (class "Default")
      (node (ref "IC2") (pin "6") (pinfunction "SCL_6") (pintype "input"))
      (node (ref "IC3") (pin "6") (pinfunction "SCL_6") (pintype "input"))
      (node (ref "IC4") (pin "6") (pinfunction "SCL_6") (pintype "input"))
      (node (ref "IC5") (pin "6") (pinfunction "SCL_6") (pintype "input"))
      (node (ref "IC7") (pin "1") (pinfunction "SCL_1") (pintype "bidirectional"))
      (node (ref "IC8") (pin "1") (pinfunction "SCLK_1") (pintype "input"))
      (node (ref "JP5") (pin "10") (pinfunction "10_10") (pintype "passive"))
      (node (ref "JP8") (pin "1") (pinfunction "1_1") (pintype "passive"))
      (node (ref "R10") (pin "1") (pinfunction "1_1") (pintype "passive"))
      (node (ref "R2") (pin "1") (pinfunction "1_1") (pintype "passive"))
      (node (ref "U$4") (pin "18") (pinfunction "18_18") (pintype "passive"))
    )
    (net (code "9") (name "A6") (class "Default")
      (node (ref "R38") (pin "1") (pinfunction "1_1") (pintype "passive"))
      (node (ref "SJ12") (pin "2") (pinfunction "2_2") (pintype "passive"))
      (node (ref "SJ8") (pin "2") (pinfunction "2_2") (pintype "passive"))
      (node (ref "U$4") (pin "19") (pinfunction "19_19") (pintype "passive"))
    )
    (net (code "10") (name "A7") (class "Default")
      (node (ref "R37") (pin "1") (pinfunction "1_1") (pintype "passive"))
      (node (ref "SJ11") (pin "2") (pinfunction "2_2") (pintype "passive"))
      (node (ref "SJ7") (pin "2") (pinfunction "2_2") (pintype "passive"))
      (node (ref "U$4") (pin "20") (pinfunction "20_20") (pintype "passive"))
    )
    (net (code "11") (name "A8") (class "Default")
      (node (ref "R36") (pin "1") (pinfunction "1_1") (pintype "passive"))
      (node (ref "U$4") (pin "21") (pinfunction "21_21") (pintype "passive"))
    )
    (net (code "12") (name "A9") (class "Default")
      (node (ref "R35") (pin "1") (pinfunction "1_1") (pintype "passive"))
      (node (ref "U$4") (pin "22") (pinfunction "22_22") (pintype "passive"))
    )
    (net (code "13") (name "A10") (class "Default")
      (node (ref "R42") (pin "1") (pinfunction "1_1") (pintype "passive"))
      (node (ref "U$4") (pin "2") (pinfunction "2_2") (pintype "passive"))
    )
    (net (code "14") (name "A11") (class "Default")
      (node (ref "R41") (pin "1") (pinfunction "1_1") (pintype "passive"))
      (node (ref "U$4") (pin "3") (pinfunction "3_3") (pintype "passive"))
    )
    (net (code "15") (name "A12") (class "Default")
      (node (ref "R40") (pin "1") (pinfunction "1_1") (pintype "passive"))
      (node (ref "U$4") (pin "4") (pinfunction "4_4") (pintype "passive"))
    )
    (net (code "16") (name "A13") (class "Default")
      (node (ref "R39") (pin "1") (pinfunction "1_1") (pintype "passive"))
      (node (ref "U$4") (pin "5") (pinfunction "5_5") (pintype "passive"))
    )
    (net (code "17") (name "AGND") (class "Default")
      (node (ref "JP3") (pin "13") (pinfunction "13_13") (pintype "passive"))
      (node (ref "U$4") (pin "24") (pinfunction "24_24") (pintype "passive"))
    )
    (net (code "18") (name "AREF") (class "Default")
      (node (ref "JP18") (pin "6") (pinfunction "6_6") (pintype "passive"))
      (node (ref "SJ15") (pin "2") (pinfunction "2_2") (pintype "passive"))
      (node (ref "U$4") (pin "7") (pinfunction "7_7") (pintype "passive"))
    )
    (net (code "19") (name "BAT_CHARGER") (class "Default")
      (node (ref "C17") (pin "1") (pinfunction "1_1") (pintype "passive"))
      (node (ref "IC9") (pin "18") (pinfunction "IN1_18") (pintype "input"))
      (node (ref "IC9") (pin "19") (pinfunction "IN1_19") (pintype "input"))
      (node (ref "X4") (pin "1") (pinfunction "1_1") (pintype "passive"))
      (node (ref "X4") (pin "3") (pinfunction "3_3") (pintype "passive"))
    )
    (net (code "20") (name "CE") (class "Default")
      (node (ref "IC9") (pin "17") (pinfunction "CE_17") (pintype "input"))
      (node (ref "SJ24") (pin "2") (pinfunction "2_2") (pintype "passive"))
    )
    (net (code "21") (name "D0") (class "Default")
      (node (ref "JP7") (pin "1") (pinfunction "1_1") (pintype "passive"))
      (node (ref "R13") (pin "1") (pinfunction "1_1") (pintype "passive"))
      (node (ref "SJ25") (pin "1") (pinfunction "1_1") (pintype "passive"))
      (node (ref "SJ29") (pin "1") (pinfunction "1_1") (pintype "passive"))
      (node (ref "U$3") (pin "24") (pinfunction "24_24") (pintype "passive"))
    )
    (net (code "22") (name "D1") (class "Default")
      (node (ref "JP7") (pin "2") (pinfunction "2_2") (pintype "passive"))
      (node (ref "R14") (pin "1") (pinfunction "1_1") (pintype "passive"))
      (node (ref "SJ20") (pin "2") (pinfunction "2_2") (pintype "passive"))
      (node (ref "SJ30") (pin "1") (pinfunction "1_1") (pintype "passive"))
      (node (ref "U$3") (pin "23") (pinfunction "23_23") (pintype "passive"))
    )
    (net (code "23") (name "D2") (class "Default")
      (node (ref "JP7") (pin "3") (pinfunction "3_3") (pintype "passive"))
      (node (ref "R15") (pin "1") (pinfunction "1_1") (pintype "passive"))
      (node (ref "U$3") (pin "22") (pinfunction "22_22") (pintype "passive"))
    )
    (net (code "24") (name "D3") (class "Default")
      (node (ref "JP7") (pin "4") (pinfunction "4_4") (pintype "passive"))
      (node (ref "R16") (pin "1") (pinfunction "1_1") (pintype "passive"))
      (node (ref "U$3") (pin "21") (pinfunction "21_21") (pintype "passive"))
    )
    (net (code "25") (name "D4") (class "Default")
      (node (ref "JP7") (pin "5") (pinfunction "5_5") (pintype "passive"))
      (node (ref "R17") (pin "1") (pinfunction "1_1") (pintype "passive"))
      (node (ref "SJ3") (pin "2") (pinfunction "2_2") (pintype "passive"))
      (node (ref "U$3") (pin "20") (pinfunction "20_20") (pintype "passive"))
    )
    (net (code "26") (name "D5") (class "Default")
      (node (ref "JP7") (pin "6") (pinfunction "6_6") (pintype "passive"))
      (node (ref "R18") (pin "1") (pinfunction "1_1") (pintype "passive"))
      (node (ref "SJ4") (pin "2") (pinfunction "2_2") (pintype "passive"))
      (node (ref "U$3") (pin "19") (pinfunction "19_19") (pintype "passive"))
    )
    (net (code "27") (name "D6") (class "Default")
      (node (ref "JP7") (pin "7") (pinfunction "7_7") (pintype "passive"))
      (node (ref "R19") (pin "1") (pinfunction "1_1") (pintype "passive"))
      (node (ref "SJ16") (pin "1") (pinfunction "1_1") (pintype "passive"))
      (node (ref "SJ17") (pin "1") (pinfunction "1_1") (pintype "passive"))
      (node (ref "U$3") (pin "18") (pinfunction "18_18") (pintype "passive"))
    )
    (net (code "28") (name "D7") (class "Default")
      (node (ref "IC6") (pin "1") (pinfunction "RO_1") (pintype "output"))
      (node (ref "JP7") (pin "8") (pinfunction "8_8") (pintype "passive"))
      (node (ref "R20") (pin "1") (pinfunction "1_1") (pintype "passive"))
      (node (ref "SJ26") (pin "2") (pinfunction "2_2") (pintype "passive"))
      (node (ref "U$3") (pin "17") (pinfunction "17_17") (pintype "passive"))
    )
    (net (code "29") (name "D8") (class "Default")
      (node (ref "IC6") (pin "4") (pinfunction "DI_4") (pintype "input"))
      (node (ref "JP5") (pin "1") (pinfunction "1_1") (pintype "passive"))
      (node (ref "R5") (pin "1") (pinfunction "1_1") (pintype "passive"))
      (node (ref "SJ27") (pin "1") (pinfunction "1_1") (pintype "passive"))
      (node (ref "U$3") (pin "16") (pinfunction "16_16") (pintype "passive"))
    )
    (net (code "30") (name "D9") (class "Default")
      (node (ref "JP5") (pin "2") (pinfunction "2_2") (pintype "passive"))
      (node (ref "R6") (pin "1") (pinfunction "1_1") (pintype "passive"))
      (node (ref "SJ19") (pin "1") (pinfunction "1_1") (pintype "passive"))
      (node (ref "SJ5") (pin "2") (pinfunction "2_2") (pintype "passive"))
      (node (ref "SJ9") (pin "2") (pinfunction "2_2") (pintype "passive"))
      (node (ref "U$3") (pin "15") (pinfunction "15_15") (pintype "passive"))
    )
    (net (code "31") (name "D10") (class "Default")
      (node (ref "JP5") (pin "3") (pinfunction "3_3") (pintype "passive"))
      (node (ref "R7") (pin "1") (pinfunction "1_1") (pintype "passive"))
      (node (ref "SJ10") (pin "2") (pinfunction "2_2") (pintype "passive"))
      (node (ref "SJ18") (pin "1") (pinfunction "1_1") (pintype "passive"))
      (node (ref "SJ6") (pin "2") (pinfunction "2_2") (pintype "passive"))
      (node (ref "U$3") (pin "14") (pinfunction "14_14") (pintype "passive"))
    )
    (net (code "32") (name "D11") (class "Default")
      (node (ref "JP4") (pin "5") (pinfunction "5_5") (pintype "passive"))
      (node (ref "JP4") (pin "6") (pinfunction "6_6") (pintype "passive"))
      (node (ref "JP5") (pin "4") (pinfunction "4_4") (pintype "passive"))
      (node (ref "JP9") (pin "4") (pinfunction "4_4") (pintype "passive"))
      (node (ref "R8") (pin "1") (pinfunction "1_1") (pintype "passive"))
      (node (ref "U$3") (pin "13") (pinfunction "13_13") (pintype "passive"))
      (node (ref "U1") (pin "3") (pinfunction "DATA_IN_3") (pintype "input"))
    )
    (net (code "33") (name "D12") (class "Default")
      (node (ref "JP2") (pin "11") (pinfunction "11_11") (pintype "passive"))
      (node (ref "JP2") (pin "12") (pinfunction "12_12") (pintype "passive"))
      (node (ref "JP5") (pin "5") (pinfunction "5_5") (pintype "passive"))
      (node (ref "JP9") (pin "1") (pinfunction "1_1") (pintype "passive"))
      (node (ref "R9") (pin "1") (pinfunction "1_1") (pintype "passive"))
      (node (ref "U$3") (pin "12") (pinfunction "12_12") (pintype "passive"))
      (node (ref "U1") (pin "7") (pinfunction "DATA_OUT_7") (pintype "output"))
    )
    (net (code "34") (name "D13") (class "Default")
      (node (ref "JP4") (pin "7") (pinfunction "7_7") (pintype "passive"))
      (node (ref "JP4") (pin "8") (pinfunction "8_8") (pintype "passive"))
      (node (ref "JP5") (pin "6") (pinfunction "6_6") (pintype "passive"))
      (node (ref "JP9") (pin "3") (pinfunction "3_3") (pintype "passive"))
      (node (ref "R24") (pin "1") (pinfunction "1_1") (pintype "passive"))
      (node (ref "U$4") (pin "12") (pinfunction "12_12") (pintype "passive"))
      (node (ref "U1") (pin "5") (pinfunction "SCLK_5") (pintype "input"))
    )
    (net (code "35") (name "D24") (class "Default")
      (node (ref "R25") (pin "1") (pinfunction "1_1") (pintype "passive"))
      (node (ref "U$3") (pin "11") (pinfunction "11_11") (pintype "passive"))
    )
    (net (code "36") (name "D25") (class "Default")
      (node (ref "R26") (pin "1") (pinfunction "1_1") (pintype "passive"))
      (node (ref "U$3") (pin "10") (pinfunction "10_10") (pintype "passive"))
    )
    (net (code "37") (name "D26") (class "Default")
      (node (ref "R27") (pin "1") (pinfunction "1_1") (pintype "passive"))
      (node (ref "U$3") (pin "9") (pinfunction "9_9") (pintype "passive"))
    )
    (net (code "38") (name "D27") (class "Default")
      (node (ref "R28") (pin "1") (pinfunction "1_1") (pintype "passive"))
      (node (ref "U$3") (pin "8") (pinfunction "8_8") (pintype "passive"))
    )
    (net (code "39") (name "D28") (class "Default")
      (node (ref "R29") (pin "1") (pinfunction "1_1") (pintype "passive"))
      (node (ref "U$3") (pin "7") (pinfunction "7_7") (pintype "passive"))
    )
    (net (code "40") (name "D29") (class "Default")
      (node (ref "R30") (pin "1") (pinfunction "1_1") (pintype "passive"))
      (node (ref "U$3") (pin "6") (pinfunction "6_6") (pintype "passive"))
    )
    (net (code "41") (name "D30") (class "Default")
      (node (ref "R31") (pin "1") (pinfunction "1_1") (pintype "passive"))
      (node (ref "U$3") (pin "5") (pinfunction "5_5") (pintype "passive"))
    )
    (net (code "42") (name "D31") (class "Default")
      (node (ref "R32") (pin "1") (pinfunction "1_1") (pintype "passive"))
      (node (ref "U$3") (pin "4") (pinfunction "4_4") (pintype "passive"))
    )
    (net (code "43") (name "D32") (class "Default")
      (node (ref "R33") (pin "1") (pinfunction "1_1") (pintype "passive"))
      (node (ref "U$3") (pin "3") (pinfunction "3_3") (pintype "passive"))
    )
    (net (code "44") (name "D33") (class "Default")
      (node (ref "R34") (pin "1") (pinfunction "1_1") (pintype "passive"))
      (node (ref "U$3") (pin "2") (pinfunction "2_2") (pintype "passive"))
    )
    (net (code "45") (name "DIO0") (class "Default")
      (node (ref "U$1") (pin "20") (pinfunction "DIO0_20") (pintype "bidirectional"))
      (node (ref "X6") (pin "2") (pinfunction "2_2") (pintype "passive"))
    )
    (net (code "46") (name "DIO1") (class "Default")
      (node (ref "U$1") (pin "19") (pinfunction "DIO1_19") (pintype "bidirectional"))
      (node (ref "X6") (pin "4") (pinfunction "4_4") (pintype "passive"))
    )
    (net (code "47") (name "DIO2") (class "Default")
      (node (ref "U$1") (pin "18") (pinfunction "DIO2_18") (pintype "bidirectional"))
      (node (ref "X6") (pin "6") (pinfunction "6_6") (pintype "passive"))
    )
    (net (code "48") (name "DIO3") (class "Default")
      (node (ref "U$1") (pin "17") (pinfunction "DIO3_17") (pintype "bidirectional"))
      (node (ref "X6") (pin "8") (pinfunction "8_8") (pintype "passive"))
    )
    (net (code "49") (name "DIO4") (class "Default")
      (node (ref "U$1") (pin "11") (pinfunction "DIO4_11") (pintype "bidirectional"))
      (node (ref "X6") (pin "20") (pinfunction "20_20") (pintype "passive"))
    )
    (net (code "50") (name "DIO5") (class "Default")
      (node (ref "U$1") (pin "15") (pinfunction "DIO5_15") (pintype "bidirectional"))
      (node (ref "X6") (pin "12") (pinfunction "12_12") (pintype "passive"))
    )
    (net (code "51") (name "DIO9") (class "Default")
      (node (ref "U$1") (pin "13") (pinfunction "DIO9_13") (pintype "bidirectional"))
      (node (ref "X6") (pin "16") (pinfunction "16_16") (pintype "passive"))
    )
    (net (code "52") (name "DIO11") (class "Default")
      (node (ref "U$1") (pin "7") (pinfunction "DIO11_7") (pintype "bidirectional"))
      (node (ref "X6") (pin "13") (pinfunction "13_13") (pintype "passive"))
    )
    (net (code "53") (name "DIO12") (class "Default")
      (node (ref "U$1") (pin "4") (pinfunction "DIO12_4") (pintype "bidirectional"))
      (node (ref "X6") (pin "7") (pinfunction "7_7") (pintype "passive"))
    )
    (net (code "54") (name "EXT_RESET") (class "Default")
      (node (ref "JP11") (pin "2") (pinfunction "2_2") (pintype "passive"))
      (node (ref "JP6") (pin "6") (pinfunction "6_6") (pintype "passive"))
      (node (ref "R3") (pin "1") (pinfunction "1_1") (pintype "passive"))
      (node (ref "S1") (pin "3") (pinfunction "3_3") (pintype "passive"))
      (node (ref "S1") (pin "4") (pinfunction "4_4") (pintype "passive"))
    )
    (net (code "55") (name "GND") (class "Default")
      (node (ref "BAT1") (pin "GND") (pinfunction "-_GND") (pintype "power_in"))
      (node (ref "C1") (pin "-") (pinfunction "-_-") (pintype "passive"))
      (node (ref "C10") (pin "-") (pinfunction "-_-") (pintype "passive"))
      (node (ref "C11") (pin "2") (pinfunction "2_2") (pintype "passive"))
      (node (ref "C12") (pin "2") (pinfunction "2_2") (pintype "passive"))
      (node (ref "C13") (pin "2") (pinfunction "2_2") (pintype "passive"))
      (node (ref "C16") (pin "2") (pinfunction "2_2") (pintype "passive"))
      (node (ref "C17") (pin "2") (pinfunction "2_2") (pintype "passive"))
      (node (ref "C2") (pin "-") (pinfunction "-_-") (pintype "passive"))
      (node (ref "C3") (pin "-") (pinfunction "-_-") (pintype "passive"))
      (node (ref "C4") (pin "2") (pinfunction "2_2") (pintype "passive"))
      (node (ref "C5") (pin "2") (pinfunction "2_2") (pintype "passive"))
      (node (ref "C6") (pin "2") (pinfunction "2_2") (pintype "passive"))
      (node (ref "C7") (pin "2") (pinfunction "2_2") (pintype "passive"))
      (node (ref "C8") (pin "2") (pinfunction "2_2") (pintype "passive"))
      (node (ref "C9") (pin "-") (pinfunction "-_-") (pintype "passive"))
      (node (ref "CN1") (pin "2") (pinfunction "1_2") (pintype "passive"))
      (node (ref "CN2") (pin "GND") (pinfunction "GND_GND") (pintype "power_in"))
      (node (ref "CN2") (pin "GNDBREAK") (pinfunction "GNDBREAK_GNDBREAK") (pintype "power_in"))
      (node (ref "CN3") (pin "2") (pinfunction "1_2") (pintype "passive"))
      (node (ref "D1") (pin "A") (pinfunction "A_A") (pintype "passive"))
      (node (ref "IC1") (pin "2") (pinfunction "GND_2") (pintype "passive"))
      (node (ref "IC2") (pin "1") (pinfunction "A0_1") (pintype "input"))
      (node (ref "IC2") (pin "2") (pinfunction "A1_2") (pintype "input"))
      (node (ref "IC2") (pin "4") (pinfunction "GND_4") (pintype "power_in"))
      (node (ref "IC2") (pin "7") (pinfunction "WP_7") (pintype "input"))
      (node (ref "IC3") (pin "1") (pinfunction "A0_1") (pintype "input"))
      (node (ref "IC3") (pin "4") (pinfunction "GND_4") (pintype "power_in"))
      (node (ref "IC3") (pin "7") (pinfunction "WP_7") (pintype "input"))
      (node (ref "IC4") (pin "2") (pinfunction "A1_2") (pintype "input"))
      (node (ref "IC4") (pin "4") (pinfunction "GND_4") (pintype "power_in"))
      (node (ref "IC4") (pin "7") (pinfunction "WP_7") (pintype "input"))
      (node (ref "IC5") (pin "4") (pinfunction "GND_4") (pintype "power_in"))
      (node (ref "IC5") (pin "7") (pinfunction "WP_7") (pintype "input"))
      (node (ref "IC6") (pin "5") (pinfunction "GND_5") (pintype "power_in"))
      (node (ref "IC7") (pin "2") (pinfunction "GND_2") (pintype "power_in"))
      (node (ref "IC7") (pin "4") (pinfunction "ADD0_4") (pintype "input"))
      (node (ref "IC8") (pin "2") (pinfunction "GND_2") (pintype "power_in"))
      (node (ref "IC9") (pin "10") (pinfunction "GND1_10") (pintype "power_in"))
      (node (ref "IC9") (pin "11") (pinfunction "GND1_11") (pintype "power_in"))
      (node (ref "IC9") (pin "21") (pinfunction "GND1_21") (pintype "power_in"))
      (node (ref "IC9") (pin "22") (pinfunction "GND1_22") (pintype "power_in"))
      (node (ref "IC9") (pin "P$1") (pinfunction "GND1_P$1") (pintype "power_in"))
      (node (ref "IC9") (pin "P$2") (pinfunction "GND1_P$2") (pintype "power_in"))
      (node (ref "IC9") (pin "P$3") (pinfunction "GND1_P$3") (pintype "power_in"))
      (node (ref "IC9") (pin "P$4") (pinfunction "GND1_P$4") (pintype "power_in"))
      (node (ref "JP1") (pin "14") (pinfunction "14_14") (pintype "passive"))
      (node (ref "JP16") (pin "3") (pinfunction "3_3") (pintype "passive"))
      (node (ref "JP18") (pin "9") (pinfunction "9_9") (pintype "passive"))
      (node (ref "JP2") (pin "1") (pinfunction "1_1") (pintype "passive"))
      (node (ref "JP2") (pin "2") (pinfunction "2_2") (pintype "passive"))
      (node (ref "JP4") (pin "1") (pinfunction "1_1") (pintype "passive"))
      (node (ref "JP4") (pin "2") (pinfunction "2_2") (pintype "passive"))
      (node (ref "JP4") (pin "3") (pinfunction "3_3") (pintype "passive"))
      (node (ref "JP4") (pin "4") (pinfunction "4_4") (pintype "passive"))
      (node (ref "JP5") (pin "7") (pinfunction "7_7") (pintype "passive"))
      (node (ref "JP6") (pin "2") (pinfunction "2_2") (pintype "passive"))
      (node (ref "JP6") (pin "3") (pinfunction "3_3") (pintype "passive"))
      (node (ref "JP9") (pin "6") (pinfunction "6_6") (pintype "passive"))
      (node (ref "P13") (pin "C") (pinfunction "C_C") (pintype "passive"))
      (node (ref "P8") (pin "C") (pinfunction "C_C") (pintype "passive"))
      (node (ref "P9") (pin "C") (pinfunction "C_C") (pintype "passive"))
      (node (ref "Q1") (pin "2") (pinfunction "S_2") (pintype "bidirectional"))
      (node (ref "Q2") (pin "2") (pinfunction "S_2") (pintype "bidirectional"))
      (node (ref "Q3") (pin "2") (pinfunction "S_2") (pintype "bidirectional"))
      (node (ref "Q4") (pin "2") (pinfunction "S_2") (pintype "bidirectional"))
      (node (ref "Q5") (pin "2") (pinfunction "S_2") (pintype "bidirectional"))
      (node (ref "Q6") (pin "2") (pinfunction "S_2") (pintype "bidirectional"))
      (node (ref "Q7") (pin "2") (pinfunction "S_2") (pintype "bidirectional"))
      (node (ref "R44") (pin "2") (pinfunction "2_2") (pintype "passive"))
      (node (ref "R45") (pin "1") (pinfunction "1_1") (pintype "passive"))
      (node (ref "R49") (pin "2") (pinfunction "2_2") (pintype "passive"))
      (node (ref "R50") (pin "2") (pinfunction "2_2") (pintype "passive"))
      (node (ref "R51") (pin "2") (pinfunction "2_2") (pintype "passive"))
      (node (ref "R52") (pin "2") (pinfunction "2_2") (pintype "passive"))
      (node (ref "S1") (pin "1") (pinfunction "1_1") (pintype "passive"))
      (node (ref "S1") (pin "2") (pinfunction "2_2") (pintype "passive"))
      (node (ref "SJ21") (pin "1") (pinfunction "1_1") (pintype "passive"))
      (node (ref "SJ22") (pin "1") (pinfunction "1_1") (pintype "passive"))
      (node (ref "SJ23") (pin "1") (pinfunction "1_1") (pintype "passive"))
      (node (ref "SJ24") (pin "1") (pinfunction "1_1") (pintype "passive"))
      (node (ref "U$1") (pin "10") (pinfunction "GND_10") (pintype "power_in"))
      (node (ref "U$3") (pin "25") (pinfunction "25_25") (pintype "passive"))
      (node (ref "U$4") (pin "10") (pinfunction "10_10") (pintype "passive"))
      (node (ref "U1") (pin "6") (pinfunction "VSS_6") (pintype "power_in"))
      (node (ref "U1") (pin "MT1") (pinfunction "GND_MT1") (pintype "power_in"))
      (node (ref "U1") (pin "MT2") (pinfunction "GND1_MT2") (pintype "power_in"))
      (node (ref "X1") (pin "2") (pinfunction "KL_2") (pintype "passive"))
      (node (ref "X2") (pin "1") (pinfunction "KL_1") (pintype "passive"))
      (node (ref "X6") (pin "19") (pinfunction "19_19") (pintype "passive"))
    )
    (net (code "56") (name "Net-(C10-Pad+)") (class "Default")
      (node (ref "C10") (pin "+") (pinfunction "+_+") (pintype "passive"))
      (node (ref "SJ14") (pin "2") (pinfunction "2_2") (pintype "passive"))
    )
    (net (code "57") (name "Net-(CN1-2)") (class "Default")
      (node (ref "CN1") (pin "1") (pinfunction "2_1") (pintype "passive"))
      (node (ref "CN2") (pin "PWR") (pinfunction "PWR_PWR") (pintype "power_in"))
      (node (ref "F2") (pin "+") (pinfunction "P$1_+") (pintype "bidirectional"))
      (node (ref "SJ1") (pin "2") (pinfunction "2_2") (pintype "passive"))
      (node (ref "X1") (pin "1") (pinfunction "KL_1") (pintype "passive"))
    )
    (net (code "58") (name "Net-(CN3-2)") (class "Default")
      (node (ref "C16") (pin "1") (pinfunction "1_1") (pintype "passive"))
      (node (ref "CN3") (pin "1") (pinfunction "2_1") (pintype "passive"))
      (node (ref "IC9") (pin "14") (pinfunction "VBAT1_14") (pintype "output"))
      (node (ref "IC9") (pin "15") (pinfunction "VBAT1_15") (pintype "output"))
      (node (ref "IC9") (pin "16") (pinfunction "VBAT1_16") (pintype "output"))
    )
    (net (code "59") (name "Net-(F1-P$2)") (class "Default")
      (node (ref "F1") (pin "-") (pinfunction "P$2_-") (pintype "bidirectional"))
      (node (ref "JP15") (pin "2") (pinfunction "2_2") (pintype "passive"))
      (node (ref "SJ14") (pin "1") (pinfunction "1_1") (pintype "passive"))
    )
    (net (code "60") (name "Net-(F2-P$2)") (class "Default")
      (node (ref "D1") (pin "C") (pinfunction "C_C") (pintype "passive"))
      (node (ref "F2") (pin "-") (pinfunction "P$2_-") (pintype "bidirectional"))
      (node (ref "SJ1") (pin "1") (pinfunction "1_1") (pintype "passive"))
      (node (ref "X3") (pin "2") (pinfunction "2_2") (pintype "passive"))
      (node (ref "X3") (pin "4") (pinfunction "4_4") (pintype "passive"))
    )
    (net (code "61") (name "Net-(IC1-VI)") (class "Default")
      (node (ref "C1") (pin "+") (pinfunction "+_+") (pintype "passive"))
      (node (ref "D2") (pin "C") (pinfunction "C_C") (pintype "passive"))
      (node (ref "IC1") (pin "1") (pinfunction "VI_1") (pintype "input"))
      (node (ref "SJ2") (pin "2") (pinfunction "2_2") (pintype "passive"))
      (node (ref "X3") (pin "1") (pinfunction "1_1") (pintype "passive"))
    )
    (net (code "62") (name "Net-(IC1-VO)") (class "Default")
      (node (ref "C2") (pin "+") (pinfunction "+_+") (pintype "passive"))
      (node (ref "C9") (pin "+") (pinfunction "+_+") (pintype "passive"))
      (node (ref "D2") (pin "A") (pinfunction "A_A") (pintype "passive"))
      (node (ref "IC1") (pin "3") (pinfunction "VO_3") (pintype "passive"))
      (node (ref "SJ2") (pin "1") (pinfunction "1_1") (pintype "passive"))
      (node (ref "X5") (pin "2") (pinfunction "2_2") (pintype "passive"))
      (node (ref "X5") (pin "4") (pinfunction "4_4") (pintype "passive"))
    )
    (net (code "63") (name "Net-(IC6-A)") (class "Default")
      (node (ref "IC6") (pin "6") (pinfunction "A_6") (pintype "passive"))
      (node (ref "R45") (pin "2") (pinfunction "2_2") (pintype "passive"))
      (node (ref "R47") (pin "1") (pinfunction "1_1") (pintype "passive"))
      (node (ref "X2") (pin "2") (pinfunction "KL_2") (pintype "passive"))
    )
    (net (code "64") (name "Net-(IC6-B)") (class "Default")
      (node (ref "IC6") (pin "7") (pinfunction "B_7") (pintype "passive"))
      (node (ref "R46") (pin "1") (pinfunction "1_1") (pintype "passive"))
      (node (ref "R47") (pin "2") (pinfunction "2_2") (pintype "passive"))
      (node (ref "X2") (pin "3") (pinfunction "KL_3") (pintype "passive"))
    )
    (net (code "65") (name "Net-(IC6-DE)") (class "Default")
      (node (ref "IC6") (pin "3") (pinfunction "DE_3") (pintype "input"))
      (node (ref "JP14") (pin "1") (pinfunction "1_1") (pintype "passive"))
      (node (ref "SJ17") (pin "2") (pinfunction "2_2") (pintype "passive"))
      (node (ref "SJ28") (pin "2") (pinfunction "2_2") (pintype "passive"))
    )
    (net (code "66") (name "Net-(IC6-RE{slash})") (class "Default")
      (node (ref "IC6") (pin "2") (pinfunction "RE/_2") (pintype "input"))
      (node (ref "JP14") (pin "2") (pinfunction "2_2") (pintype "passive"))
      (node (ref "SJ16") (pin "2") (pinfunction "2_2") (pintype "passive"))
    )
    (net (code "67") (name "Net-(IC7-VCC)") (class "Default")
      (node (ref "C12") (pin "1") (pinfunction "1_1") (pintype "passive"))
      (node (ref "IC7") (pin "5") (pinfunction "VCC_5") (pintype "power_in"))
      (node (ref "R48") (pin "1") (pinfunction "1_1") (pintype "passive"))
    )
    (net (code "68") (name "Net-(IC9-PROG1)") (class "Default")
      (node (ref "IC9") (pin "13") (pinfunction "PROG1_13") (pintype "input"))
      (node (ref "R51") (pin "1") (pinfunction "1_1") (pintype "passive"))
    )
    (net (code "69") (name "Net-(IC9-PROG3)") (class "Default")
      (node (ref "IC9") (pin "12") (pinfunction "PROG3_12") (pintype "input"))
      (node (ref "R50") (pin "1") (pinfunction "1_1") (pintype "passive"))
    )
    (net (code "70") (name "Net-(IC9-STAT1{slash}LBO)") (class "Default")
      (node (ref "IC9") (pin "8") (pinfunction "STAT1/LBO_8") (pintype "output"))
      (node (ref "P10") (pin "C") (pinfunction "C_C") (pintype "passive"))
    )
    (net (code "71") (name "Net-(IC9-STAT2)") (class "Default")
      (node (ref "IC9") (pin "7") (pinfunction "STAT2_7") (pintype "output"))
      (node (ref "P11") (pin "C") (pinfunction "C_C") (pintype "passive"))
    )
    (net (code "72") (name "Net-(IC9-THERM)") (class "Default")
      (node (ref "IC9") (pin "5") (pinfunction "THERM_5") (pintype "input"))
      (node (ref "R43") (pin "2") (pinfunction "2_2") (pintype "passive"))
    )
    (net (code "73") (name "Net-(IC9-VPCC)") (class "Default")
      (node (ref "IC9") (pin "2") (pinfunction "VPCC_2") (pintype "input"))
      (node (ref "R52") (pin "1") (pinfunction "1_1") (pintype "passive"))
      (node (ref "R53") (pin "2") (pinfunction "2_2") (pintype "passive"))
    )
    (net (code "74") (name "Net-(IC9-{slash}PG)") (class "Default")
      (node (ref "IC9") (pin "6") (pinfunction "/PG_6") (pintype "output"))
      (node (ref "P12") (pin "C") (pinfunction "C_C") (pintype "passive"))
    )
    (net (code "75") (name "Net-(JP1-Pad1)") (class "Default")
      (node (ref "JP1") (pin "1") (pinfunction "1_1") (pintype "passive"))
      (node (ref "R9") (pin "2") (pinfunction "2_2") (pintype "passive"))
    )
    (net (code "76") (name "Net-(JP1-Pad2)") (class "Default")
      (node (ref "JP1") (pin "2") (pinfunction "2_2") (pintype "passive"))
      (node (ref "R8") (pin "2") (pinfunction "2_2") (pintype "passive"))
    )
    (net (code "77") (name "Net-(JP1-Pad3)") (class "Default")
      (node (ref "JP1") (pin "3") (pinfunction "3_3") (pintype "passive"))
      (node (ref "R7") (pin "2") (pinfunction "2_2") (pintype "passive"))
    )
    (net (code "78") (name "Net-(JP1-Pad4)") (class "Default")
      (node (ref "JP1") (pin "4") (pinfunction "4_4") (pintype "passive"))
      (node (ref "R6") (pin "2") (pinfunction "2_2") (pintype "passive"))
    )
    (net (code "79") (name "Net-(JP1-Pad5)") (class "Default")
      (node (ref "JP1") (pin "5") (pinfunction "5_5") (pintype "passive"))
      (node (ref "R5") (pin "2") (pinfunction "2_2") (pintype "passive"))
    )
    (net (code "80") (name "Net-(JP1-Pad6)") (class "Default")
      (node (ref "JP1") (pin "6") (pinfunction "6_6") (pintype "passive"))
      (node (ref "R20") (pin "2") (pinfunction "2_2") (pintype "passive"))
    )
    (net (code "81") (name "Net-(JP1-Pad7)") (class "Default")
      (node (ref "JP1") (pin "7") (pinfunction "7_7") (pintype "passive"))
      (node (ref "R19") (pin "2") (pinfunction "2_2") (pintype "passive"))
    )
    (net (code "82") (name "Net-(JP1-Pad8)") (class "Default")
      (node (ref "JP1") (pin "8") (pinfunction "8_8") (pintype "passive"))
      (node (ref "R18") (pin "2") (pinfunction "2_2") (pintype "passive"))
    )
    (net (code "83") (name "Net-(JP1-Pad9)") (class "Default")
      (node (ref "JP1") (pin "9") (pinfunction "9_9") (pintype "passive"))
      (node (ref "R17") (pin "2") (pinfunction "2_2") (pintype "passive"))
    )
    (net (code "84") (name "Net-(JP1-Pad10)") (class "Default")
      (node (ref "JP1") (pin "10") (pinfunction "10_10") (pintype "passive"))
      (node (ref "R16") (pin "2") (pinfunction "2_2") (pintype "passive"))
    )
    (net (code "85") (name "Net-(JP1-Pad11)") (class "Default")
      (node (ref "JP1") (pin "11") (pinfunction "11_11") (pintype "passive"))
      (node (ref "R15") (pin "2") (pinfunction "2_2") (pintype "passive"))
    )
    (net (code "86") (name "Net-(JP1-Pad12)") (class "Default")
      (node (ref "JP1") (pin "12") (pinfunction "12_12") (pintype "passive"))
      (node (ref "R14") (pin "2") (pinfunction "2_2") (pintype "passive"))
    )
    (net (code "87") (name "Net-(JP1-Pad13)") (class "Default")
      (node (ref "JP1") (pin "13") (pinfunction "13_13") (pintype "passive"))
      (node (ref "R13") (pin "2") (pinfunction "2_2") (pintype "passive"))
    )
    (net (code "88") (name "Net-(JP2-Pad7)") (class "Default")
      (node (ref "JP2") (pin "7") (pinfunction "7_7") (pintype "passive"))
      (node (ref "JP2") (pin "8") (pinfunction "8_8") (pintype "passive"))
    )
    (net (code "89") (name "Net-(JP2-Pad10)") (class "Default")
      (node (ref "JP2") (pin "10") (pinfunction "10_10") (pintype "passive"))
      (node (ref "JP2") (pin "9") (pinfunction "9_9") (pintype "passive"))
    )
    (net (code "90") (name "Net-(JP3-Pad1)") (class "Default")
      (node (ref "JP3") (pin "1") (pinfunction "1_1") (pintype "passive"))
      (node (ref "R24") (pin "2") (pinfunction "2_2") (pintype "passive"))
    )
    (net (code "91") (name "Net-(JP3-Pad2)") (class "Default")
      (node (ref "JP3") (pin "2") (pinfunction "2_2") (pintype "passive"))
      (node (ref "R23") (pin "2") (pinfunction "2_2") (pintype "passive"))
    )
    (net (code "92") (name "Net-(JP3-Pad3)") (class "Default")
      (node (ref "JP3") (pin "3") (pinfunction "3_3") (pintype "passive"))
      (node (ref "R22") (pin "2") (pinfunction "2_2") (pintype "passive"))
    )
    (net (code "93") (name "Net-(JP3-Pad4)") (class "Default")
      (node (ref "JP3") (pin "4") (pinfunction "4_4") (pintype "passive"))
      (node (ref "R21") (pin "2") (pinfunction "2_2") (pintype "passive"))
    )
    (net (code "94") (name "Net-(JP3-Pad5)") (class "Default")
      (node (ref "JP3") (pin "5") (pinfunction "5_5") (pintype "passive"))
      (node (ref "R12") (pin "2") (pinfunction "2_2") (pintype "passive"))
    )
    (net (code "95") (name "Net-(JP3-Pad6)") (class "Default")
      (node (ref "JP3") (pin "6") (pinfunction "6_6") (pintype "passive"))
      (node (ref "R11") (pin "2") (pinfunction "2_2") (pintype "passive"))
    )
    (net (code "96") (name "Net-(JP3-Pad7)") (class "Default")
      (node (ref "JP3") (pin "7") (pinfunction "7_7") (pintype "passive"))
      (node (ref "R10") (pin "2") (pinfunction "2_2") (pintype "passive"))
    )
    (net (code "97") (name "Net-(JP3-Pad8)") (class "Default")
      (node (ref "JP3") (pin "8") (pinfunction "8_8") (pintype "passive"))
      (node (ref "R38") (pin "2") (pinfunction "2_2") (pintype "passive"))
    )
    (net (code "98") (name "Net-(JP3-Pad9)") (class "Default")
      (node (ref "JP3") (pin "9") (pinfunction "9_9") (pintype "passive"))
      (node (ref "R37") (pin "2") (pinfunction "2_2") (pintype "passive"))
    )
    (net (code "99") (name "Net-(JP3-Pad10)") (class "Default")
      (node (ref "JP3") (pin "10") (pinfunction "10_10") (pintype "passive"))
      (node (ref "R36") (pin "2") (pinfunction "2_2") (pintype "passive"))
    )
    (net (code "100") (name "Net-(JP3-Pad11)") (class "Default")
      (node (ref "JP3") (pin "11") (pinfunction "11_11") (pintype "passive"))
      (node (ref "R35") (pin "2") (pinfunction "2_2") (pintype "passive"))
    )
    (net (code "101") (name "Net-(JP4-Pad10)") (class "Default")
      (node (ref "JP4") (pin "10") (pinfunction "10_10") (pintype "passive"))
      (node (ref "JP4") (pin "9") (pinfunction "9_9") (pintype "passive"))
      (node (ref "SJ10") (pin "1") (pinfunction "1_1") (pintype "passive"))
      (node (ref "SJ11") (pin "1") (pinfunction "1_1") (pintype "passive"))
      (node (ref "SJ12") (pin "1") (pinfunction "1_1") (pintype "passive"))
      (node (ref "SJ9") (pin "1") (pinfunction "1_1") (pintype "passive"))
    )
    (net (code "102") (name "Net-(JP4-Pad11)") (class "Default")
      (node (ref "JP4") (pin "11") (pinfunction "11_11") (pintype "passive"))
      (node (ref "JP4") (pin "12") (pinfunction "12_12") (pintype "passive"))
    )
    (net (code "103") (name "Net-(JP5-Pad8)") (class "Default")
      (node (ref "JP5") (pin "8") (pinfunction "8_8") (pintype "passive"))
      (node (ref "SJ15") (pin "1") (pinfunction "1_1") (pintype "passive"))
    )
    (net (code "104") (name "Net-(JP17-Pad1)") (class "Default")
      (node (ref "JP17") (pin "1") (pinfunction "1_1") (pintype "passive"))
      (node (ref "R34") (pin "2") (pinfunction "2_2") (pintype "passive"))
    )
    (net (code "105") (name "Net-(JP17-Pad2)") (class "Default")
      (node (ref "JP17") (pin "2") (pinfunction "2_2") (pintype "passive"))
      (node (ref "R33") (pin "2") (pinfunction "2_2") (pintype "passive"))
    )
    (net (code "106") (name "Net-(JP17-Pad3)") (class "Default")
      (node (ref "JP17") (pin "3") (pinfunction "3_3") (pintype "passive"))
      (node (ref "R32") (pin "2") (pinfunction "2_2") (pintype "passive"))
    )
    (net (code "107") (name "Net-(JP17-Pad4)") (class "Default")
      (node (ref "JP17") (pin "4") (pinfunction "4_4") (pintype "passive"))
      (node (ref "R31") (pin "2") (pinfunction "2_2") (pintype "passive"))
    )
    (net (code "108") (name "Net-(JP17-Pad5)") (class "Default")
      (node (ref "JP17") (pin "5") (pinfunction "5_5") (pintype "passive"))
      (node (ref "R30") (pin "2") (pinfunction "2_2") (pintype "passive"))
    )
    (net (code "109") (name "Net-(JP17-Pad6)") (class "Default")
      (node (ref "JP17") (pin "6") (pinfunction "6_6") (pintype "passive"))
      (node (ref "R29") (pin "2") (pinfunction "2_2") (pintype "passive"))
    )
    (net (code "110") (name "Net-(JP17-Pad7)") (class "Default")
      (node (ref "JP17") (pin "7") (pinfunction "7_7") (pintype "passive"))
      (node (ref "R28") (pin "2") (pinfunction "2_2") (pintype "passive"))
    )
    (net (code "111") (name "Net-(JP17-Pad8)") (class "Default")
      (node (ref "JP17") (pin "8") (pinfunction "8_8") (pintype "passive"))
      (node (ref "R27") (pin "2") (pinfunction "2_2") (pintype "passive"))
    )
    (net (code "112") (name "Net-(JP17-Pad9)") (class "Default")
      (node (ref "JP17") (pin "9") (pinfunction "9_9") (pintype "passive"))
      (node (ref "R26") (pin "2") (pinfunction "2_2") (pintype "passive"))
    )
    (net (code "113") (name "Net-(JP17-Pad10)") (class "Default")
      (node (ref "JP17") (pin "10") (pinfunction "10_10") (pintype "passive"))
      (node (ref "R25") (pin "2") (pinfunction "2_2") (pintype "passive"))
    )
    (net (code "114") (name "Net-(JP18-Pad1)") (class "Default")
      (node (ref "JP18") (pin "1") (pinfunction "1_1") (pintype "passive"))
      (node (ref "R42") (pin "2") (pinfunction "2_2") (pintype "passive"))
    )
    (net (code "115") (name "Net-(JP18-Pad2)") (class "Default")
      (node (ref "JP18") (pin "2") (pinfunction "2_2") (pintype "passive"))
      (node (ref "R41") (pin "2") (pinfunction "2_2") (pintype "passive"))
    )
    (net (code "116") (name "Net-(JP18-Pad3)") (class "Default")
      (node (ref "JP18") (pin "3") (pinfunction "3_3") (pintype "passive"))
      (node (ref "R40") (pin "2") (pinfunction "2_2") (pintype "passive"))
    )
    (net (code "117") (name "Net-(JP18-Pad4)") (class "Default")
      (node (ref "JP18") (pin "4") (pinfunction "4_4") (pintype "passive"))
      (node (ref "R39") (pin "2") (pinfunction "2_2") (pintype "passive"))
    )
    (net (code "118") (name "Net-(P1-PadA)") (class "Default")
      (node (ref "P1") (pin "A") (pinfunction "A_A") (pintype "passive"))
      (node (ref "R61") (pin "1") (pinfunction "1_1") (pintype "passive"))
    )
    (net (code "119") (name "Net-(P2-PadA)") (class "Default")
      (node (ref "P2") (pin "A") (pinfunction "A_A") (pintype "passive"))
      (node (ref "R60") (pin "1") (pinfunction "1_1") (pintype "passive"))
    )
    (net (code "120") (name "Net-(P3-PadA)") (class "Default")
      (node (ref "P3") (pin "A") (pinfunction "A_A") (pintype "passive"))
      (node (ref "R58") (pin "1") (pinfunction "1_1") (pintype "passive"))
    )
    (net (code "121") (name "Net-(P4-PadA)") (class "Default")
      (node (ref "P4") (pin "A") (pinfunction "A_A") (pintype "passive"))
      (node (ref "R59") (pin "1") (pinfunction "1_1") (pintype "passive"))
    )
    (net (code "122") (name "Net-(P5-PadA)") (class "Default")
      (node (ref "P5") (pin "A") (pinfunction "A_A") (pintype "passive"))
      (node (ref "R57") (pin "1") (pinfunction "1_1") (pintype "passive"))
    )
    (net (code "123") (name "Net-(P6-PadA)") (class "Default")
      (node (ref "P6") (pin "A") (pinfunction "A_A") (pintype "passive"))
      (node (ref "R62") (pin "1") (pinfunction "1_1") (pintype "passive"))
    )
    (net (code "124") (name "Net-(P7-PadA)") (class "Default")
      (node (ref "P7") (pin "A") (pinfunction "A_A") (pintype "passive"))
      (node (ref "R63") (pin "1") (pinfunction "1_1") (pintype "passive"))
    )
    (net (code "125") (name "Net-(P8-PadA)") (class "Default")
      (node (ref "P8") (pin "A") (pinfunction "A_A") (pintype "passive"))
      (node (ref "R65") (pin "1") (pinfunction "1_1") (pintype "passive"))
    )
    (net (code "126") (name "Net-(P9-PadA)") (class "Default")
      (node (ref "P9") (pin "A") (pinfunction "A_A") (pintype "passive"))
      (node (ref "R64") (pin "1") (pinfunction "1_1") (pintype "passive"))
    )
    (net (code "127") (name "Net-(P10-PadA)") (class "Default")
      (node (ref "P10") (pin "A") (pinfunction "A_A") (pintype "passive"))
      (node (ref "R56") (pin "2") (pinfunction "2_2") (pintype "passive"))
    )
    (net (code "128") (name "Net-(P11-PadA)") (class "Default")
      (node (ref "P11") (pin "A") (pinfunction "A_A") (pintype "passive"))
      (node (ref "R55") (pin "2") (pinfunction "2_2") (pintype "passive"))
    )
    (net (code "129") (name "Net-(P12-PadA)") (class "Default")
      (node (ref "P12") (pin "A") (pinfunction "A_A") (pintype "passive"))
      (node (ref "R54") (pin "2") (pinfunction "2_2") (pintype "passive"))
    )
    (net (code "130") (name "Net-(P13-PadA)") (class "Default")
      (node (ref "P13") (pin "A") (pinfunction "A_A") (pintype "passive"))
      (node (ref "R66") (pin "1") (pinfunction "1_1") (pintype "passive"))
    )
    (net (code "131") (name "Net-(Q1-D)") (class "Default")
      (node (ref "P2") (pin "C") (pinfunction "C_C") (pintype "passive"))
      (node (ref "Q1") (pin "3") (pinfunction "D_3") (pintype "bidirectional"))
    )
    (net (code "132") (name "Net-(Q1-G)") (class "Default")
      (node (ref "Q1") (pin "1") (pinfunction "G_1") (pintype "bidirectional"))
      (node (ref "SJ20") (pin "1") (pinfunction "1_1") (pintype "passive"))
    )
    (net (code "133") (name "Net-(Q2-D)") (class "Default")
      (node (ref "P1") (pin "C") (pinfunction "C_C") (pintype "passive"))
      (node (ref "Q2") (pin "3") (pinfunction "D_3") (pintype "bidirectional"))
    )
    (net (code "134") (name "Net-(Q2-G)") (class "Default")
      (node (ref "Q2") (pin "1") (pinfunction "G_1") (pintype "bidirectional"))
      (node (ref "SJ25") (pin "2") (pinfunction "2_2") (pintype "passive"))
    )
    (net (code "135") (name "Net-(Q3-D)") (class "Default")
      (node (ref "P4") (pin "C") (pinfunction "C_C") (pintype "passive"))
      (node (ref "Q3") (pin "3") (pinfunction "D_3") (pintype "bidirectional"))
    )
    (net (code "136") (name "Net-(Q3-G)") (class "Default")
      (node (ref "Q3") (pin "1") (pinfunction "G_1") (pintype "bidirectional"))
      (node (ref "SJ26") (pin "1") (pinfunction "1_1") (pintype "passive"))
    )
    (net (code "137") (name "Net-(Q4-D)") (class "Default")
      (node (ref "P3") (pin "C") (pinfunction "C_C") (pintype "passive"))
      (node (ref "Q4") (pin "3") (pinfunction "D_3") (pintype "bidirectional"))
    )
    (net (code "138") (name "Net-(Q4-G)") (class "Default")
      (node (ref "Q4") (pin "1") (pinfunction "G_1") (pintype "bidirectional"))
      (node (ref "SJ27") (pin "2") (pinfunction "2_2") (pintype "passive"))
    )
    (net (code "139") (name "Net-(Q5-D)") (class "Default")
      (node (ref "P5") (pin "C") (pinfunction "C_C") (pintype "passive"))
      (node (ref "Q5") (pin "3") (pinfunction "D_3") (pintype "bidirectional"))
    )
    (net (code "140") (name "Net-(Q5-G)") (class "Default")
      (node (ref "Q5") (pin "1") (pinfunction "G_1") (pintype "bidirectional"))
      (node (ref "SJ28") (pin "1") (pinfunction "1_1") (pintype "passive"))
    )
    (net (code "141") (name "Net-(Q6-D)") (class "Default")
      (node (ref "P7") (pin "C") (pinfunction "C_C") (pintype "passive"))
      (node (ref "Q6") (pin "3") (pinfunction "D_3") (pintype "bidirectional"))
    )
    (net (code "142") (name "Net-(Q6-G)") (class "Default")
      (node (ref "Q6") (pin "1") (pinfunction "G_1") (pintype "bidirectional"))
      (node (ref "SJ19") (pin "2") (pinfunction "2_2") (pintype "passive"))
    )
    (net (code "143") (name "Net-(Q7-D)") (class "Default")
      (node (ref "P6") (pin "C") (pinfunction "C_C") (pintype "passive"))
      (node (ref "Q7") (pin "3") (pinfunction "D_3") (pintype "bidirectional"))
    )
    (net (code "144") (name "Net-(Q7-G)") (class "Default")
      (node (ref "Q7") (pin "1") (pinfunction "G_1") (pintype "bidirectional"))
      (node (ref "SJ18") (pin "2") (pinfunction "2_2") (pintype "passive"))
    )
    (net (code "145") (name "Net-(R43-Pad1)") (class "Default")
      (node (ref "R43") (pin "1") (pinfunction "1_1") (pintype "passive"))
      (node (ref "R44") (pin "1") (pinfunction "1_1") (pintype "passive"))
      (node (ref "R49") (pin "1") (pinfunction "1_1") (pintype "passive"))
    )
    (net (code "146") (name "Net-(U1-CARD_DETECT)") (class "Default")
      (node (ref "R4") (pin "1") (pinfunction "1_1") (pintype "passive"))
      (node (ref "SJ3") (pin "1") (pinfunction "1_1") (pintype "passive"))
      (node (ref "SJ4") (pin "1") (pinfunction "1_1") (pintype "passive"))
      (node (ref "U1") (pin "CD1") (pinfunction "CARD_DETECT_CD1") (pintype "passive"))
    )
    (net (code "147") (name "Net-(U1-CS)") (class "Default")
      (node (ref "SJ5") (pin "1") (pinfunction "1_1") (pintype "passive"))
      (node (ref "SJ6") (pin "1") (pinfunction "1_1") (pintype "passive"))
      (node (ref "SJ7") (pin "1") (pinfunction "1_1") (pintype "passive"))
      (node (ref "SJ8") (pin "1") (pinfunction "1_1") (pintype "passive"))
      (node (ref "U1") (pin "2") (pinfunction "CS_2") (pintype "input"))
    )
    (net (code "148") (name "Net-(X4-Pad2)") (class "Default")
      (node (ref "X4") (pin "2") (pinfunction "2_2") (pintype "passive"))
      (node (ref "X5") (pin "1") (pinfunction "1_1") (pintype "passive"))
    )
    (net (code "149") (name "PROG") (class "Default")
      (node (ref "JP11") (pin "3") (pinfunction "3_3") (pintype "passive"))
      (node (ref "JP16") (pin "2") (pinfunction "2_2") (pintype "passive"))
      (node (ref "JP18") (pin "5") (pinfunction "5_5") (pintype "passive"))
      (node (ref "U$4") (pin "6") (pinfunction "6_6") (pintype "passive"))
    )
    (net (code "150") (name "PROG2") (class "Default")
      (node (ref "IC9") (pin "4") (pinfunction "PROG2_4") (pintype "input"))
      (node (ref "SJ22") (pin "2") (pinfunction "2_2") (pintype "passive"))
    )
    (net (code "151") (name "RESET") (class "Default")
      (node (ref "JP11") (pin "1") (pinfunction "1_1") (pintype "passive"))
      (node (ref "JP16") (pin "1") (pinfunction "1_1") (pintype "passive"))
      (node (ref "JP18") (pin "7") (pinfunction "7_7") (pintype "passive"))
      (node (ref "U$4") (pin "8") (pinfunction "8_8") (pintype "passive"))
    )
    (net (code "152") (name "SEL") (class "Default")
      (node (ref "IC9") (pin "3") (pinfunction "SEL_3") (pintype "input"))
      (node (ref "SJ21") (pin "2") (pinfunction "2_2") (pintype "passive"))
    )
    (net (code "153") (name "TE") (class "Default")
      (node (ref "IC9") (pin "9") (pinfunction "/TE_9") (pintype "input"))
      (node (ref "SJ23") (pin "2") (pinfunction "2_2") (pintype "passive"))
    )
    (net (code "154") (name "VBAT") (class "Default")
      (node (ref "BAT1") (pin "PWR@1") (pinfunction "+_PWR@1") (pintype "power_in"))
      (node (ref "JP16") (pin "5") (pinfunction "5_5") (pintype "passive"))
      (node (ref "JP18") (pin "10") (pinfunction "10_10") (pintype "passive"))
      (node (ref "U$4") (pin "11") (pinfunction "11_11") (pintype "passive"))
    )
    (net (code "155") (name "VIN") (class "Default")
      (node (ref "IC9") (pin "1") (pinfunction "OUT1_1") (pintype "output"))
      (node (ref "IC9") (pin "20") (pinfunction "OUT1_20") (pintype "output"))
      (node (ref "JP15") (pin "1") (pinfunction "1_1") (pintype "passive"))
      (node (ref "JP3") (pin "14") (pinfunction "14_14") (pintype "passive"))
      (node (ref "JP6") (pin "1") (pinfunction "1_1") (pintype "passive"))
      (node (ref "U$4") (pin "25") (pinfunction "25_25") (pintype "passive"))
      (node (ref "X3") (pin "3") (pinfunction "3_3") (pintype "passive"))
    )
    (net (code "156") (name "VUSB") (class "Default")
      (node (ref "C3") (pin "+") (pinfunction "+_+") (pintype "passive"))
      (node (ref "F1") (pin "+") (pinfunction "P$1_+") (pintype "bidirectional"))
      (node (ref "JP18") (pin "8") (pinfunction "8_8") (pintype "passive"))
      (node (ref "U$4") (pin "9") (pinfunction "9_9") (pintype "passive"))
      (node (ref "X4") (pin "4") (pinfunction "4_4") (pintype "passive"))
    )
    (net (code "157") (name "XBEE_CTS") (class "Default")
      (node (ref "U$1") (pin "12") (pinfunction "CTS_12") (pintype "output"))
      (node (ref "X6") (pin "18") (pinfunction "18_18") (pintype "passive"))
    )
    (net (code "158") (name "XBEE_DIN") (class "Default")
      (node (ref "SJ30") (pin "2") (pinfunction "2_2") (pintype "passive"))
      (node (ref "U$1") (pin "3") (pinfunction "DIN_3") (pintype "input"))
      (node (ref "X6") (pin "5") (pinfunction "5_5") (pintype "passive"))
    )
    (net (code "159") (name "XBEE_DOUT") (class "Default")
      (node (ref "SJ29") (pin "2") (pinfunction "2_2") (pintype "passive"))
      (node (ref "U$1") (pin "2") (pinfunction "DOUT_2") (pintype "output"))
      (node (ref "X6") (pin "3") (pinfunction "3_3") (pintype "passive"))
    )
    (net (code "160") (name "XBEE_DTR") (class "Default")
      (node (ref "U$1") (pin "9") (pinfunction "DTR_9") (pintype "bidirectional"))
      (node (ref "X6") (pin "17") (pinfunction "17_17") (pintype "passive"))
    )
    (net (code "161") (name "XBEE_RES1") (class "Default")
      (node (ref "U$1") (pin "8") (pinfunction "RES_8") (pintype "bidirectional"))
      (node (ref "X6") (pin "15") (pinfunction "15_15") (pintype "passive"))
    )
    (net (code "162") (name "XBEE_RSSI") (class "Default")
      (node (ref "R65") (pin "2") (pinfunction "2_2") (pintype "passive"))
      (node (ref "U$1") (pin "6") (pinfunction "RSSI_6") (pintype "bidirectional"))
      (node (ref "X6") (pin "11") (pinfunction "11_11") (pintype "passive"))
    )
    (net (code "163") (name "XBEE_RST") (class "Default")
      (node (ref "U$1") (pin "5") (pinfunction "RESET_5") (pintype "input"))
      (node (ref "X6") (pin "9") (pinfunction "9_9") (pintype "passive"))
    )
    (net (code "164") (name "XBEE_RTS") (class "Default")
      (node (ref "R64") (pin "2") (pinfunction "2_2") (pintype "passive"))
      (node (ref "U$1") (pin "16") (pinfunction "RTS_16") (pintype "input"))
      (node (ref "X6") (pin "10") (pinfunction "10_10") (pintype "passive"))
    )
    (net (code "165") (name "XBEE_VREF") (class "Default")
      (node (ref "U$1") (pin "14") (pinfunction "RES_14") (pintype "bidirectional"))
      (node (ref "X6") (pin "14") (pinfunction "14_14") (pintype "passive"))
    )
    (net (code "166") (name "unconnected-(IC7-ALERT-Pad3)") (class "Default")
      (node (ref "IC7") (pin "3") (pinfunction "ALERT_3") (pintype "output"))
    )
    (net (code "167") (name "unconnected-(IC8-SDO-Pad8)") (class "Default")
      (node (ref "IC8") (pin "8") (pinfunction "SDO_8") (pintype "output"))
    )
    (net (code "168") (name "unconnected-(JP6-Pad8)") (class "Default")
      (node (ref "JP6") (pin "8") (pinfunction "8_8") (pintype "passive"))
    )
    (net (code "169") (name "unconnected-(JP9-Pad2)") (class "Default")
      (node (ref "JP9") (pin "2") (pinfunction "2_2") (pintype "passive"))
    )
    (net (code "170") (name "unconnected-(JP9-Pad5)") (class "Default")
      (node (ref "JP9") (pin "5") (pinfunction "5_5") (pintype "passive"))
    )
    (net (code "171") (name "unconnected-(U1-CARD_DETECT1-PadCD2)") (class "Default")
      (node (ref "U1") (pin "CD2") (pinfunction "CARD_DETECT1_CD2") (pintype "passive"))
    )
    (net (code "172") (name "unconnected-(U1-DAT1-Pad8)") (class "Default")
      (node (ref "U1") (pin "8") (pinfunction "DAT1_8") (pintype "bidirectional"))
    )
    (net (code "173") (name "unconnected-(U1-DAT2-Pad1)") (class "Default")
      (node (ref "U1") (pin "1") (pinfunction "DAT2_1") (pintype "bidirectional"))
    )
  )
)
